# tempContr.net
KiCad netlist of a schematic drawn in Altium Designer
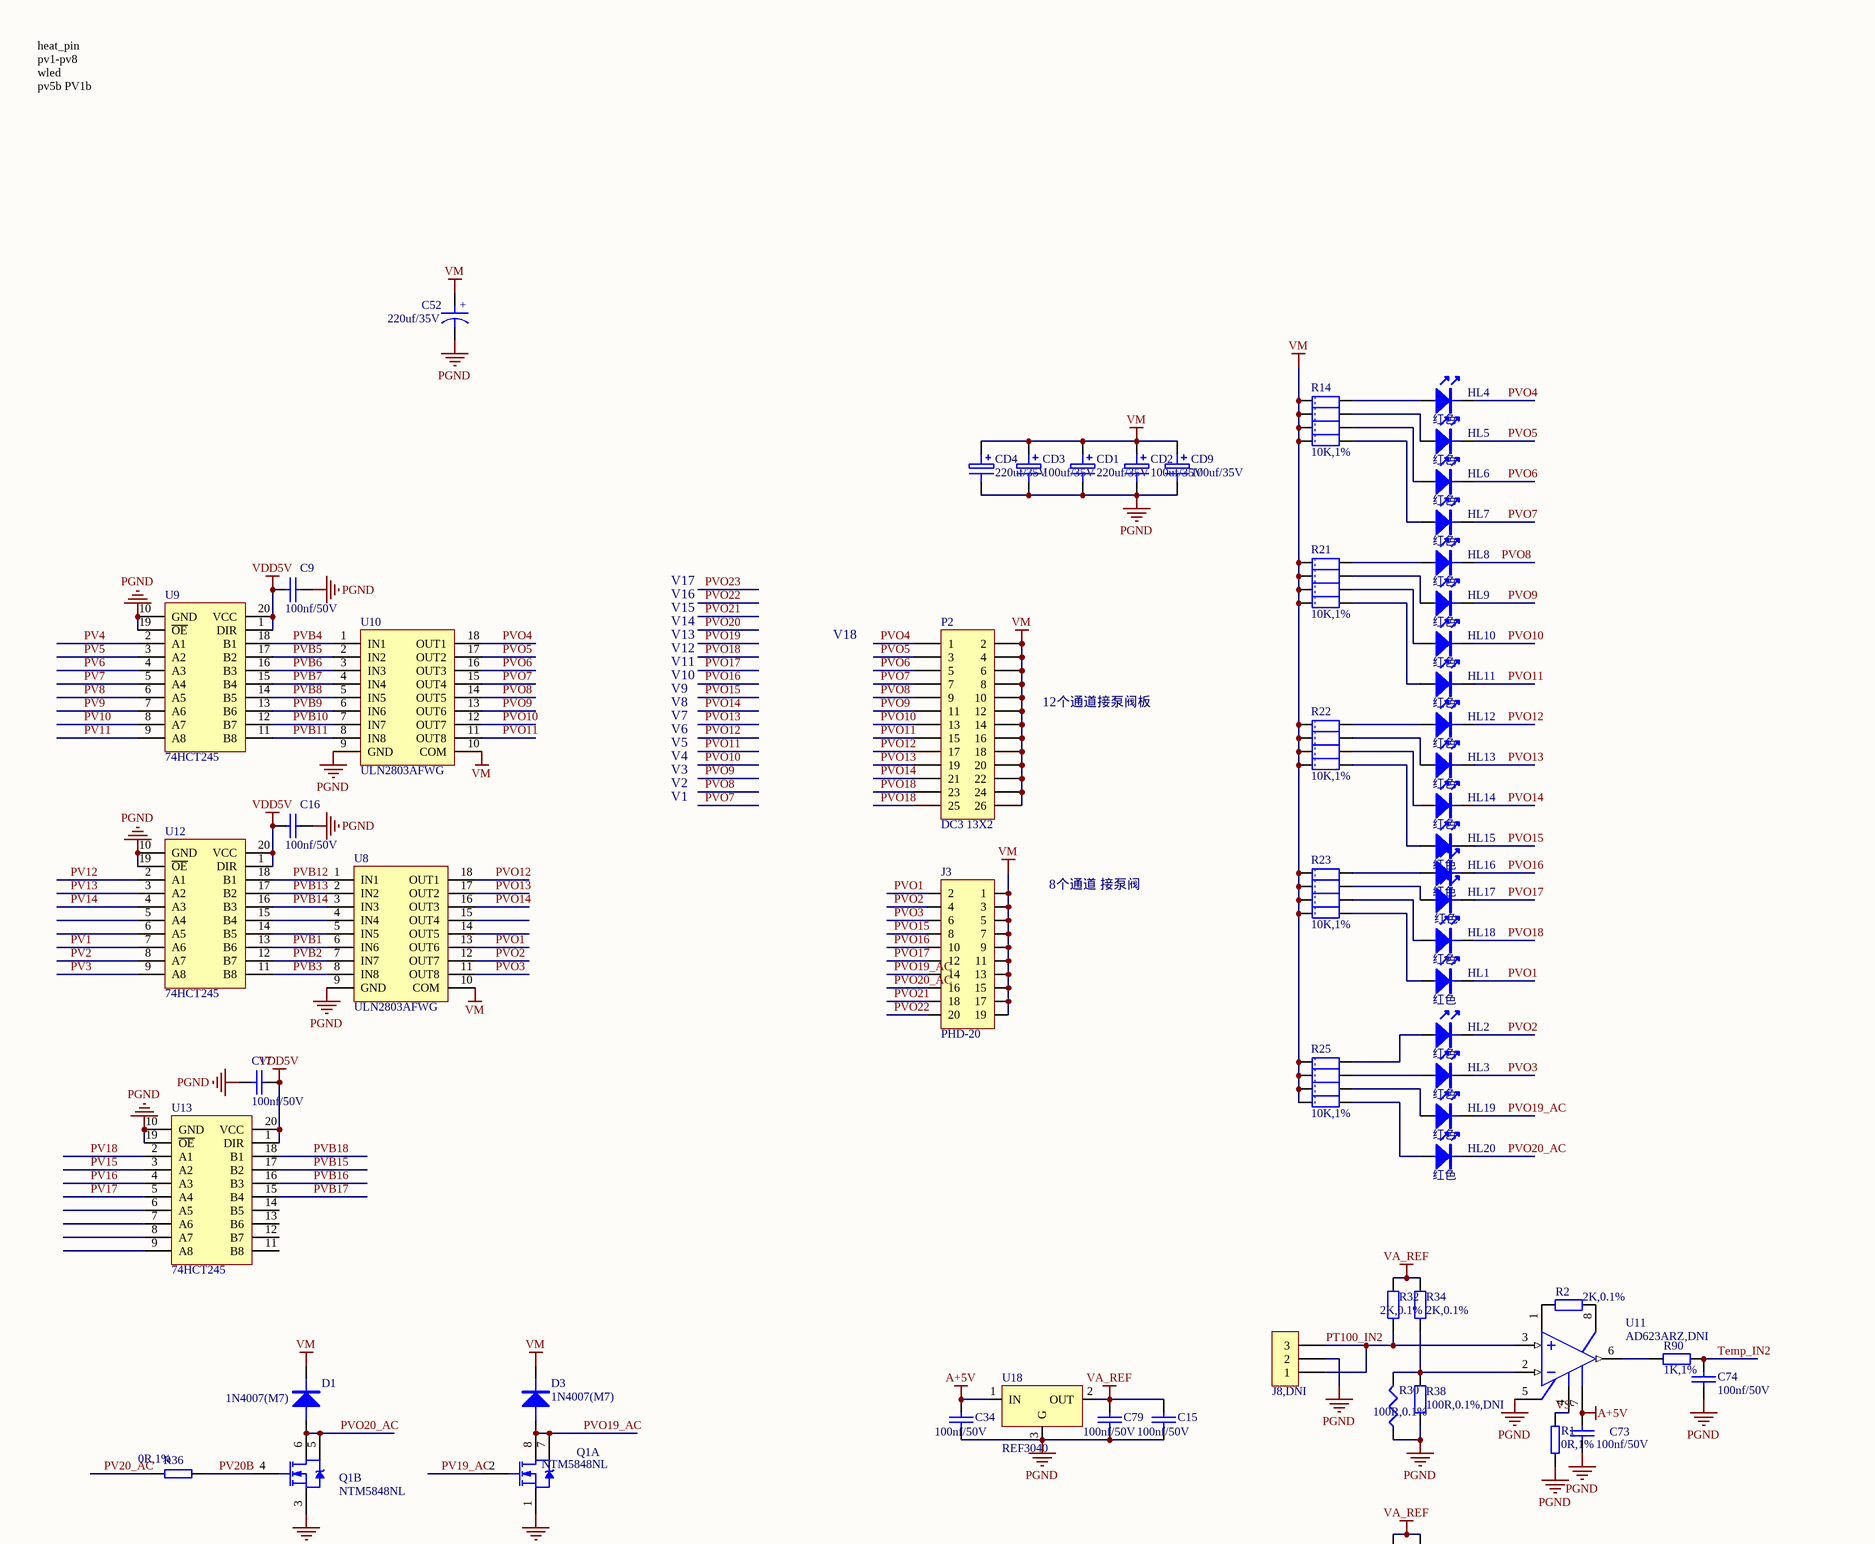
[diagram p0: tempContr.SchDoc, top left]
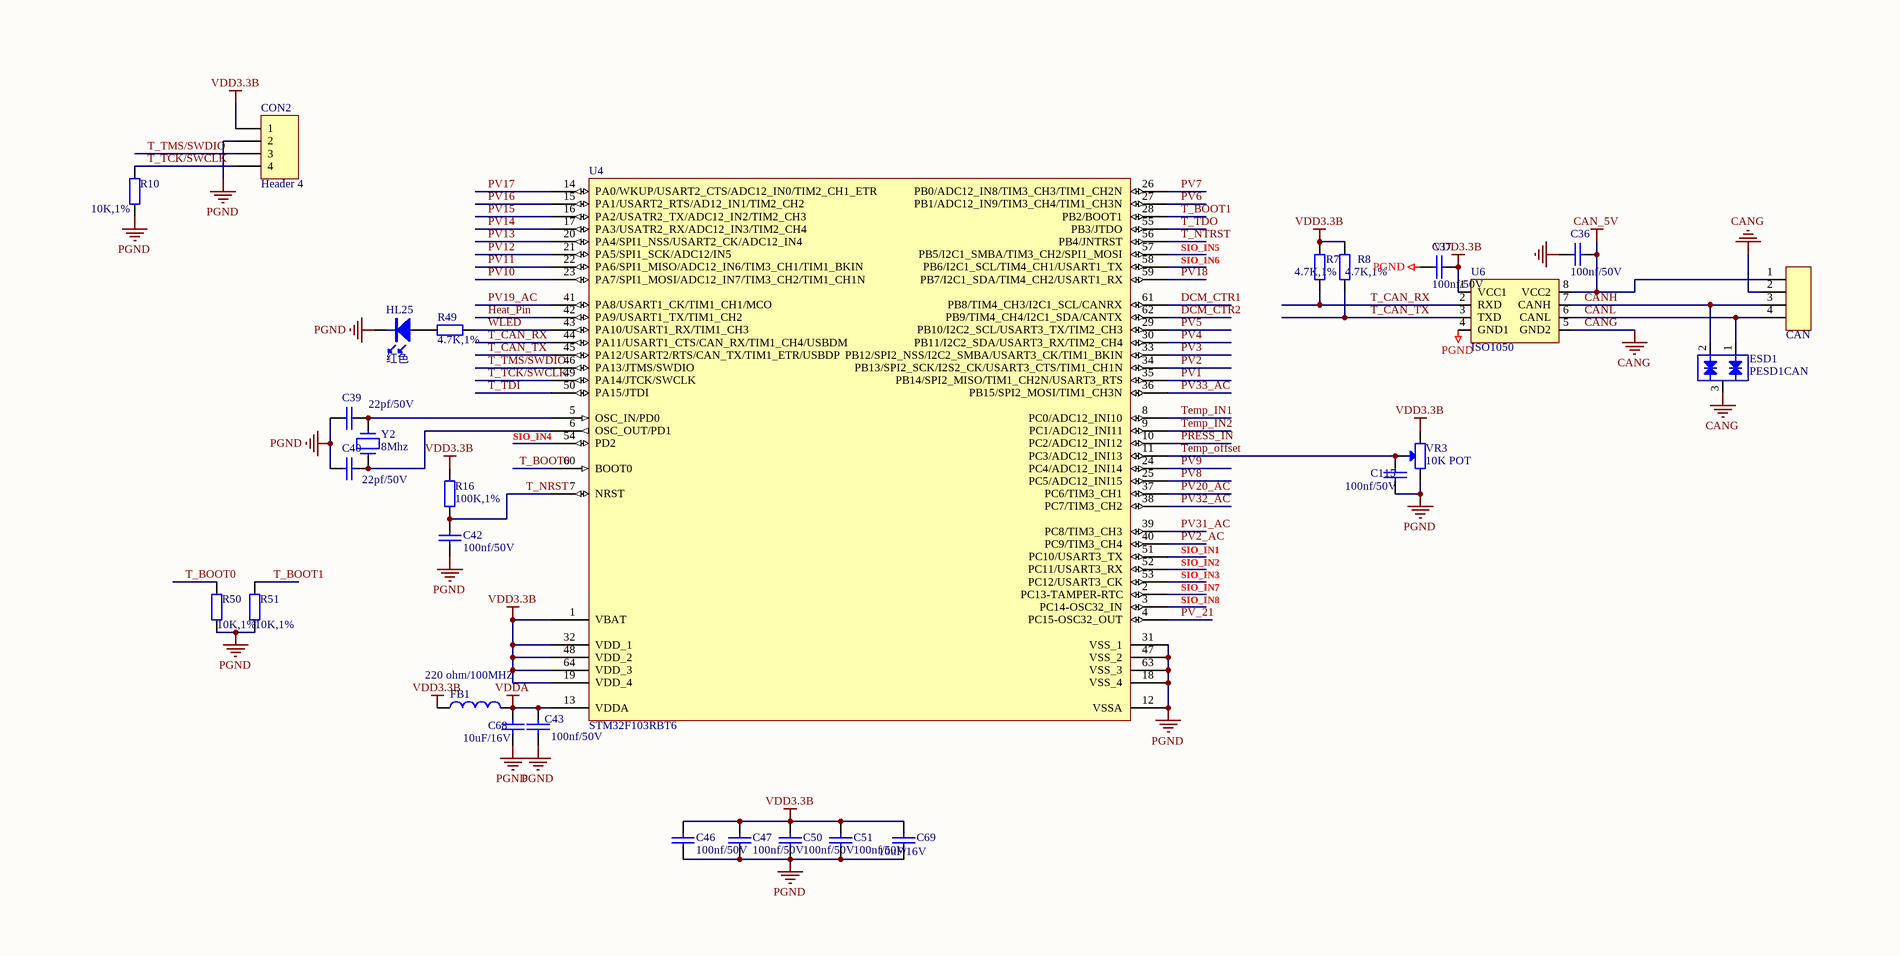
[diagram p1: tempContr.SchDoc, top right]
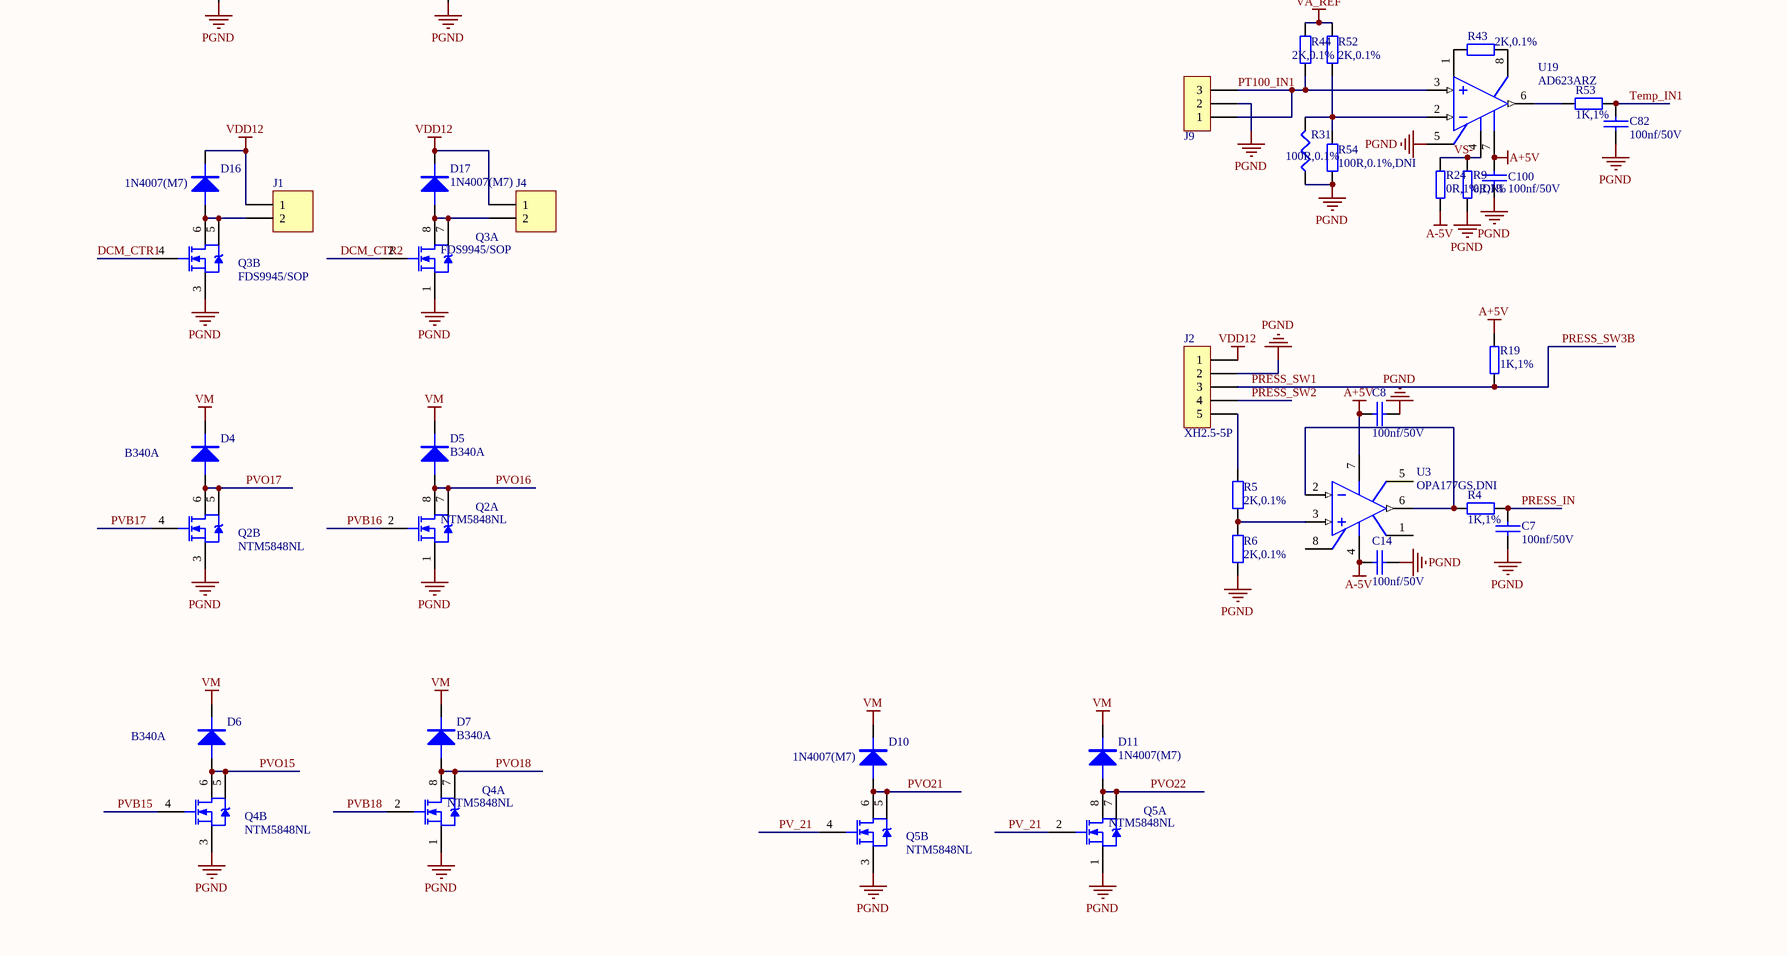
[diagram p2: tempContr.SchDoc, bottom left]
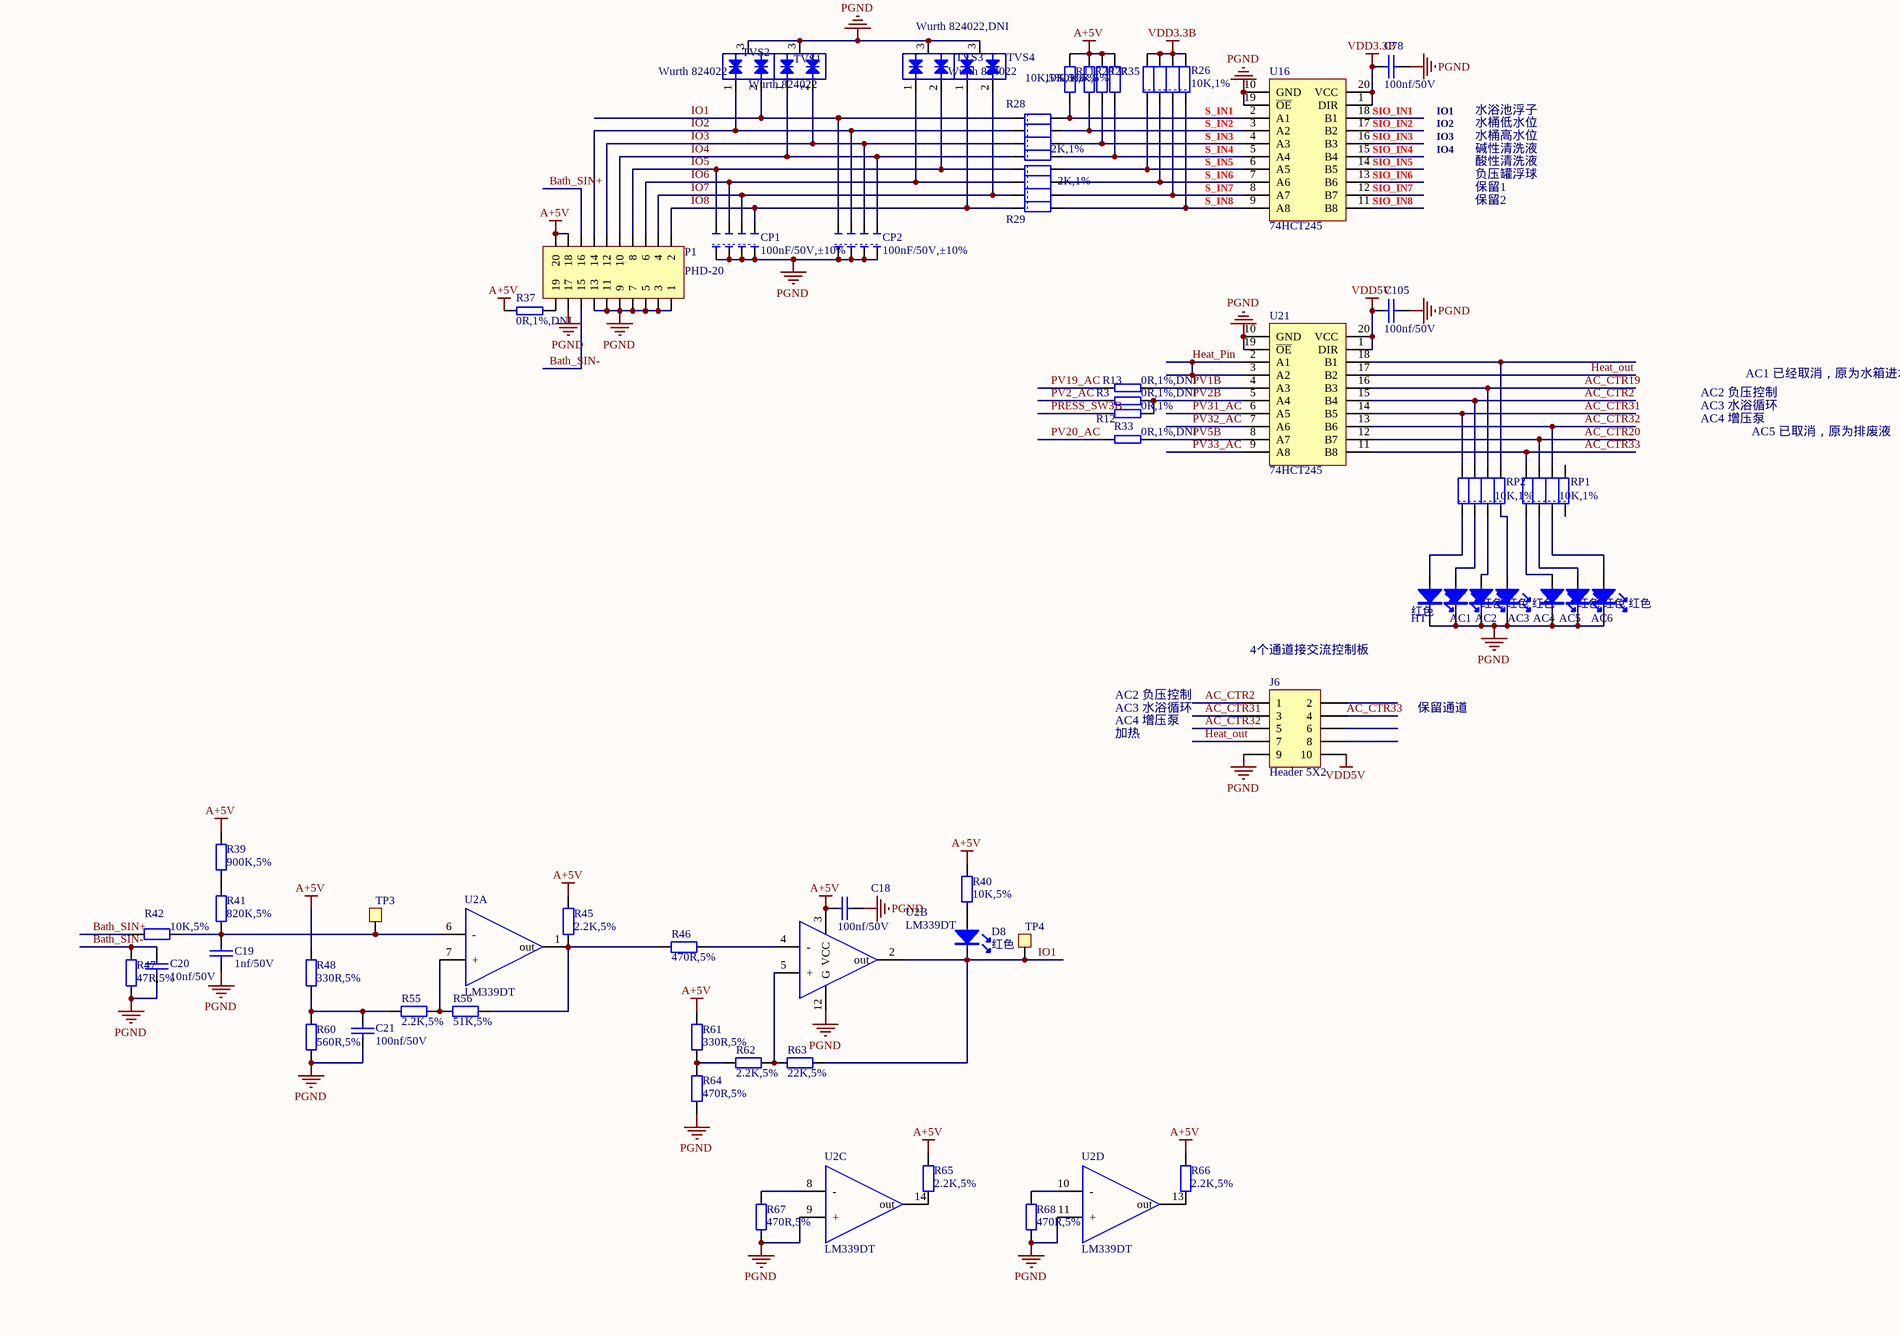
[diagram p3: tempContr.SchDoc, bottom right]

(export (version "E")
  (design (tool "Eeschema 10.0.6"))
  (components
    (comp (ref "AC1")
      (value "红色")
      (footprint "LED_0805")
      (description "Led")
      (fields (field (name "Comment") "LED,Red"))
      (libsource (lib "DiscreteCom") (part "LED"))
    )
    (comp (ref "AC2")
      (value "红色")
      (footprint "LED_0805")
      (description "Led")
      (fields (field (name "Comment") "LED,Red"))
      (libsource (lib "DiscreteCom") (part "LED"))
    )
    (comp (ref "AC3")
      (value "红色")
      (footprint "LED_0805")
      (description "Led")
      (fields (field (name "Comment") "LED,Red"))
      (libsource (lib "DiscreteCom") (part "LED"))
    )
    (comp (ref "AC4")
      (value "红色")
      (footprint "LED_0805")
      (description "Led")
      (fields (field (name "Comment") "LED,Red"))
      (libsource (lib "DiscreteCom") (part "LED"))
    )
    (comp (ref "AC5")
      (value "红色")
      (footprint "LED_0805")
      (description "Led")
      (fields (field (name "Comment") "LED,Red"))
      (libsource (lib "DiscreteCom") (part "LED"))
    )
    (comp (ref "AC6")
      (value "红色")
      (footprint "LED_0805")
      (description "Led")
      (fields (field (name "Comment") "LED,Red"))
      (libsource (lib "DiscreteCom") (part "LED"))
    )
    (comp (ref "C7")
      (value "100nf/50V")
      (footprint "0805")
      (description "Capacitor")
      (libsource (lib "DiscreteCom") (part "CAP"))
    )
    (comp (ref "C8")
      (value "100nf/50V")
      (footprint "0805")
      (description "Capacitor")
      (libsource (lib "*") (part "CAP"))
    )
    (comp (ref "C9")
      (value "100nf/50V")
      (footprint "0805")
      (description "Capacitor")
      (libsource (lib "*") (part "CAP"))
    )
    (comp (ref "C14")
      (value "100nf/50V")
      (footprint "0805")
      (description "Capacitor")
      (libsource (lib "*") (part "CAP"))
    )
    (comp (ref "C15")
      (value "100nf/50V")
      (footprint "0805")
      (description "Capacitor")
      (libsource (lib "*") (part "CAP"))
    )
    (comp (ref "C16")
      (value "100nf/50V")
      (footprint "0805")
      (description "Capacitor")
      (libsource (lib "*") (part "CAP"))
    )
    (comp (ref "C17")
      (value "100nf/50V")
      (footprint "0805")
      (description "Capacitor")
      (libsource (lib "*") (part "CAP"))
    )
    (comp (ref "C18")
      (value "100nf/50V")
      (footprint "0805")
      (description "Capacitor")
      (libsource (lib "DiscreteCom") (part "CAP"))
    )
    (comp (ref "C19")
      (value "1nf/50V")
      (footprint "0805")
      (description "Capacitor")
      (libsource (lib "DiscreteCom") (part "CAP"))
    )
    (comp (ref "C20")
      (value "10nf/50V")
      (footprint "0805")
      (description "Capacitor")
      (libsource (lib "DiscreteCom") (part "CAP"))
    )
    (comp (ref "C21")
      (value "100nf/50V")
      (footprint "0805")
      (description "Capacitor")
      (libsource (lib "DiscreteCom") (part "CAP"))
    )
    (comp (ref "C34")
      (value "100nf/50V")
      (footprint "0805")
      (description "Capacitor")
      (libsource (lib "*") (part "CAP"))
    )
    (comp (ref "C36")
      (value "100nf/50V")
      (footprint "0805")
      (description "Capacitor")
      (libsource (lib "DiscreteCom") (part "CAP"))
    )
    (comp (ref "C37")
      (value "100nf/50V")
      (footprint "0805")
      (description "Capacitor")
      (libsource (lib "DiscreteCom") (part "CAP"))
    )
    (comp (ref "C39")
      (value "22pf/50V")
      (footprint "0805")
      (description "Capacitor")
      (libsource (lib "DiscreteCom") (part "CAP"))
    )
    (comp (ref "C40")
      (value "22pf/50V")
      (footprint "0805")
      (description "Capacitor")
      (libsource (lib "DiscreteCom") (part "CAP"))
    )
    (comp (ref "C42")
      (value "100nf/50V")
      (footprint "0805")
      (description "Capacitor")
      (libsource (lib "DiscreteCom") (part "CAP"))
    )
    (comp (ref "C43")
      (value "100nf/50V")
      (footprint "0805")
      (description "Capacitor")
      (libsource (lib "DiscreteCom") (part "CAP"))
    )
    (comp (ref "C46")
      (value "100nf/50V")
      (footprint "0805")
      (description "Capacitor")
      (libsource (lib "DiscreteCom") (part "CAP"))
    )
    (comp (ref "C47")
      (value "100nf/50V")
      (footprint "0805")
      (description "Capacitor")
      (libsource (lib "DiscreteCom") (part "CAP"))
    )
    (comp (ref "C50")
      (value "100nf/50V")
      (footprint "0805")
      (description "Capacitor")
      (libsource (lib "DiscreteCom") (part "CAP"))
    )
    (comp (ref "C51")
      (value "100nf/50V")
      (footprint "0805")
      (description "Capacitor")
      (libsource (lib "DiscreteCom") (part "CAP"))
    )
    (comp (ref "C52")
      (value "220uf/35V")
      (footprint "CX8*10.5")
      (description "Capacitor")
      (libsource (lib "General") (part "CAPACITOR POL"))
    )
    (comp (ref "C68")
      (value "10uF/16V")
      (footprint "GeneralPcblib V0.1:1206")
      (description "Capacitor")
      (libsource (lib "General") (part "CAP"))
    )
    (comp (ref "C69")
      (value "10uF/16V")
      (footprint "GeneralPcblib V0.1:1206")
      (description "Capacitor")
      (libsource (lib "General") (part "CAP"))
    )
    (comp (ref "C73")
      (value "100nf/50V")
      (footprint "0805")
      (description "Capacitor")
      (libsource (lib "*") (part "CAP"))
    )
    (comp (ref "C74")
      (value "100nf/50V")
      (footprint "0805")
      (description "Capacitor")
      (libsource (lib "DiscreteCom") (part "CAP"))
    )
    (comp (ref "C78")
      (value "100nf/50V")
      (footprint "0805")
      (description "Capacitor")
      (libsource (lib "*") (part "CAP"))
    )
    (comp (ref "C79")
      (value "100nf/50V")
      (footprint "0805")
      (description "Capacitor")
      (libsource (lib "*") (part "CAP"))
    )
    (comp (ref "C82")
      (value "100nf/50V")
      (footprint "0805")
      (description "Capacitor")
      (libsource (lib "DiscreteCom") (part "CAP"))
    )
    (comp (ref "C100")
      (value "100nf/50V")
      (footprint "0805")
      (description "Capacitor")
      (libsource (lib "*") (part "CAP"))
    )
    (comp (ref "C105")
      (value "100nf/50V")
      (footprint "0805")
      (description "Capacitor")
      (libsource (lib "*") (part "CAP"))
    )
    (comp (ref "C115")
      (value "100nf/50V")
      (footprint "0805")
      (description "Capacitor")
      (libsource (lib "DiscreteCom") (part "CAP"))
    )
    (comp (ref "CAN")
      (value "XH2.54-4P")
      (footprint "GeneralPcblib V0.1:XH2.5-4P")
      (description "XH2.54-4P 针座")
      (libsource (lib "CON1") (part "XH2.54-4P"))
    )
    (comp (ref "CD1")
      (value "220uf/35V")
      (footprint "CX8*10.5")
      (description "Electrolytic Capacitor")
      (libsource (lib "DiscreteCom") (part "Capacitor Electrolytic"))
    )
    (comp (ref "CD2")
      (value "100uf/35V")
      (footprint "CX6.3*5.4")
      (description "Electrolytic Capacitor")
      (libsource (lib "DiscreteCom") (part "Capacitor Electrolytic"))
    )
    (comp (ref "CD3")
      (value "100uf/35V")
      (footprint "CX6.3*5.4")
      (description "Electrolytic Capacitor")
      (libsource (lib "DiscreteCom") (part "Capacitor Electrolytic"))
    )
    (comp (ref "CD4")
      (value "220uf/35V")
      (footprint "CX8*10.5")
      (description "Electrolytic Capacitor")
      (libsource (lib "DiscreteCom") (part "Capacitor Electrolytic"))
    )
    (comp (ref "CD9")
      (value "100uf/35V")
      (footprint "CX6.3*5.4")
      (description "Electrolytic Capacitor")
      (libsource (lib "DiscreteCom") (part "Capacitor Electrolytic"))
    )
    (comp (ref "CON2")
      (value "Header 4")
      (footprint "HDR1X4")
      (description "Header, 4-Pin")
      (fields (field (name "PUBLISHER") "Altium Limited"))
      (libsource (lib "Miscellaneous Connectors") (part "Header 4"))
    )
    (comp (ref "CP1")
      (value "100nF/50V,±10%")
      (footprint "8P4R_0603")
      (libsource (lib "DiscreteCom") (part "CAP 1*4"))
    )
    (comp (ref "CP2")
      (value "100nF/50V,±10%")
      (footprint "8P4R_0603")
      (libsource (lib "DiscreteCom") (part "CAP 1*4"))
    )
    (comp (ref "D1")
      (value "1N4007(M7)")
      (footprint "GeneralPcblib V0.1:SMA(AK)")
      (description "Diode")
      (libsource (lib "General") (part "DIODE"))
    )
    (comp (ref "D3")
      (value "1N4007(M7)")
      (footprint "GeneralPcblib V0.1:SMA(AK)")
      (description "Diode")
      (libsource (lib "General") (part "DIODE"))
    )
    (comp (ref "D4")
      (value "B340A")
      (footprint "GeneralPcblib V0.1:SMA(AK)")
      (description "Diode")
      (libsource (lib "General") (part "DIODE"))
    )
    (comp (ref "D5")
      (value "B340A")
      (footprint "GeneralPcblib V0.1:SMA(AK)")
      (description "Diode")
      (libsource (lib "General") (part "DIODE"))
    )
    (comp (ref "D6")
      (value "B340A")
      (footprint "GeneralPcblib V0.1:SMA(AK)")
      (description "Diode")
      (libsource (lib "General") (part "DIODE"))
    )
    (comp (ref "D7")
      (value "B340A")
      (footprint "GeneralPcblib V0.1:SMA(AK)")
      (description "Diode")
      (libsource (lib "General") (part "DIODE"))
    )
    (comp (ref "D8")
      (value "红色")
      (footprint "LED_0805")
      (description "Led")
      (fields (field (name "Comment") "LED"))
      (libsource (lib "") (part "LED_1"))
    )
    (comp (ref "D10")
      (value "1N4007(M7)")
      (footprint "GeneralPcblib V0.1:SMA(AK)")
      (description "Diode")
      (libsource (lib "General") (part "DIODE"))
    )
    (comp (ref "D11")
      (value "1N4007(M7)")
      (footprint "GeneralPcblib V0.1:SMA(AK)")
      (description "Diode")
      (libsource (lib "General") (part "DIODE"))
    )
    (comp (ref "D16")
      (value "1N4007(M7)")
      (footprint "GeneralPcblib V0.1:SMA(AK)")
      (description "Diode")
      (libsource (lib "General") (part "DIODE"))
    )
    (comp (ref "D17")
      (value "1N4007(M7)")
      (footprint "GeneralPcblib V0.1:SMA(AK)")
      (description "Diode")
      (libsource (lib "General") (part "DIODE"))
    )
    (comp (ref "ESD1")
      (value "PESD1CAN")
      (footprint "SOT233")
      (description "Diode")
      (libsource (lib "DiscreteCom") (part "TVS-2"))
    )
    (comp (ref "FB1")
      (value "220 ohm/100MHZ")
      (footprint "GeneralPcblib V0.1:0805")
      (description "Inductor")
      (libsource (lib "DiscreteCom") (part "INDUCTOR"))
    )
    (comp (ref "HL1")
      (value "红色")
      (footprint "LED_0805")
      (description "Led")
      (fields (field (name "Comment") "LED,Red"))
      (libsource (lib "DiscreteCom") (part "LED"))
    )
    (comp (ref "HL2")
      (value "红色")
      (footprint "LED_0805")
      (description "Led")
      (fields (field (name "Comment") "LED,Red"))
      (libsource (lib "DiscreteCom") (part "LED"))
    )
    (comp (ref "HL3")
      (value "红色")
      (footprint "LED_0805")
      (description "Led")
      (fields (field (name "Comment") "LED,Red"))
      (libsource (lib "DiscreteCom") (part "LED"))
    )
    (comp (ref "HL4")
      (value "红色")
      (footprint "LED_0805")
      (description "Led")
      (fields (field (name "Comment") "LED,Red"))
      (libsource (lib "DiscreteCom") (part "LED"))
    )
    (comp (ref "HL5")
      (value "红色")
      (footprint "LED_0805")
      (description "Led")
      (fields (field (name "Comment") "LED,Red"))
      (libsource (lib "DiscreteCom") (part "LED"))
    )
    (comp (ref "HL6")
      (value "红色")
      (footprint "LED_0805")
      (description "Led")
      (fields (field (name "Comment") "LED,Red"))
      (libsource (lib "DiscreteCom") (part "LED"))
    )
    (comp (ref "HL7")
      (value "红色")
      (footprint "LED_0805")
      (description "Led")
      (fields (field (name "Comment") "LED,Red"))
      (libsource (lib "DiscreteCom") (part "LED"))
    )
    (comp (ref "HL8")
      (value "红色")
      (footprint "LED_0805")
      (description "Led")
      (fields (field (name "Comment") "LED,Red"))
      (libsource (lib "DiscreteCom") (part "LED"))
    )
    (comp (ref "HL9")
      (value "红色")
      (footprint "LED_0805")
      (description "Led")
      (fields (field (name "Comment") "LED,Red"))
      (libsource (lib "DiscreteCom") (part "LED"))
    )
    (comp (ref "HL10")
      (value "红色")
      (footprint "LED_0805")
      (description "Led")
      (fields (field (name "Comment") "LED,Red"))
      (libsource (lib "DiscreteCom") (part "LED"))
    )
    (comp (ref "HL11")
      (value "红色")
      (footprint "LED_0805")
      (description "Led")
      (fields (field (name "Comment") "LED,Red"))
      (libsource (lib "DiscreteCom") (part "LED"))
    )
    (comp (ref "HL12")
      (value "红色")
      (footprint "LED_0805")
      (description "Led")
      (fields (field (name "Comment") "LED,Red"))
      (libsource (lib "DiscreteCom") (part "LED"))
    )
    (comp (ref "HL13")
      (value "红色")
      (footprint "LED_0805")
      (description "Led")
      (fields (field (name "Comment") "LED,Red"))
      (libsource (lib "DiscreteCom") (part "LED"))
    )
    (comp (ref "HL14")
      (value "红色")
      (footprint "LED_0805")
      (description "Led")
      (fields (field (name "Comment") "LED,Red"))
      (libsource (lib "DiscreteCom") (part "LED"))
    )
    (comp (ref "HL15")
      (value "红色")
      (footprint "LED_0805")
      (description "Led")
      (fields (field (name "Comment") "LED,Red"))
      (libsource (lib "DiscreteCom") (part "LED"))
    )
    (comp (ref "HL16")
      (value "红色")
      (footprint "LED_0805")
      (description "Led")
      (fields (field (name "Comment") "LED,Red"))
      (libsource (lib "DiscreteCom") (part "LED"))
    )
    (comp (ref "HL17")
      (value "红色")
      (footprint "LED_0805")
      (description "Led")
      (fields (field (name "Comment") "LED,Red"))
      (libsource (lib "DiscreteCom") (part "LED"))
    )
    (comp (ref "HL18")
      (value "红色")
      (footprint "LED_0805")
      (description "Led")
      (fields (field (name "Comment") "LED,Red"))
      (libsource (lib "DiscreteCom") (part "LED"))
    )
    (comp (ref "HL19")
      (value "红色")
      (footprint "LED_0805")
      (description "Led")
      (fields (field (name "Comment") "LED,Red"))
      (libsource (lib "DiscreteCom") (part "LED"))
    )
    (comp (ref "HL20")
      (value "红色")
      (footprint "LED_0805")
      (description "Led")
      (fields (field (name "Comment") "LED,Red"))
      (libsource (lib "DiscreteCom") (part "LED"))
    )
    (comp (ref "HL25")
      (value "红色")
      (footprint "LED_0805")
      (description "Led")
      (fields (field (name "Comment") "LED,Red"))
      (libsource (lib "DiscreteCom") (part "LED"))
    )
    (comp (ref "HT")
      (value "红色")
      (footprint "LED_0805")
      (description "Led")
      (fields (field (name "Comment") "LED,Red"))
      (libsource (lib "DiscreteCom") (part "LED"))
    )
    (comp (ref "J1")
      (value "XH2.54-2P")
      (footprint "GeneralPcblib V0.1:XH2.5-2P")
      (description "XH2.54-2P 针座")
      (fields (field (name "PUBLISHER") "Altium Limited"))
      (libsource (lib "CON1") (part "XH2.54-2P"))
    )
    (comp (ref "J2")
      (value "XH2.5-5P")
      (footprint "GeneralPcblib V0.1:XH2.5-5P")
      (description "XH2.5-5P 针座")
      (libsource (lib "CON1") (part "XH2.54-5P"))
    )
    (comp (ref "J3")
      (value "PHD-20")
      (footprint "PHD-20")
      (description "PHD-20针座")
      (fields (field (name "PUBLISHER") "Altium Limited"))
      (libsource (lib "CON1") (part "PHD-20"))
    )
    (comp (ref "J4")
      (value "XH2.54-2P")
      (footprint "GeneralPcblib V0.1:XH2.5-2P")
      (description "XH2.54-2P 针座")
      (fields (field (name "PUBLISHER") "Altium Limited"))
      (libsource (lib "CON1") (part "XH2.54-2P"))
    )
    (comp (ref "J6")
      (value "Header 5X2")
      (footprint "DC3-10")
      (description "Header, 5-Pin, Dual row")
      (fields (field (name "PUBLISHER") "Altium Limited"))
      (libsource (lib "Miscellaneous Connectors") (part "Header 5X2"))
    )
    (comp (ref "J8,DNI")
      (value "XH2.54-3P")
      (footprint "GeneralPcblib V0.1:XH2.5-3P")
      (description "XH2.54-3P 针座")
      (libsource (lib "CON1") (part "XH2.54-3P"))
    )
    (comp (ref "J9")
      (value "XH2.54-3P")
      (footprint "GeneralPcblib V0.1:XH2.5-3P")
      (description "XH2.54-3P 针座")
      (libsource (lib "CON1") (part "XH2.54-3P"))
    )
    (comp (ref "P1")
      (value "PHD-20")
      (footprint "PHD-20")
      (description "PHD-20针座")
      (fields (field (name "PUBLISHER") "Altium Limited"))
      (libsource (lib "") (part "PHD-20_1"))
    )
    (comp (ref "P2")
      (value "DC3 13X2")
      (footprint "GeneralPcblib V0.1:DC3-2X13")
      (description "Header, 13-Pin, Dual row")
      (fields (field (name "PUBLISHER") "Altium Limited"))
      (libsource (lib "Miscellaneous Connectors") (part "Header 13X2"))
    )
    (comp (ref "Q1")
      (value "NTM5848NL")
      (footprint "SOIC8")
      (description "N-Channel Power MOSFET")
      (fields (field (name "PUBLISHER") "Altium Limited"))
      (libsource (lib "DiscreteCom") (part "NMOS-9945"))
    )
    (comp (ref "Q2")
      (value "NTM5848NL")
      (footprint "SOIC8")
      (description "N-Channel Power MOSFET")
      (fields (field (name "PUBLISHER") "Altium Limited"))
      (libsource (lib "DiscreteCom") (part "NMOS-9945"))
    )
    (comp (ref "Q3")
      (value "FDS9945/SOP")
      (footprint "SOIC8")
      (description "N-Channel Power MOSFET")
      (fields (field (name "PUBLISHER") "Altium Limited"))
      (libsource (lib "DiscreteCom") (part "NMOS-9945"))
    )
    (comp (ref "Q4")
      (value "NTM5848NL")
      (footprint "SOIC8")
      (description "N-Channel Power MOSFET")
      (fields (field (name "PUBLISHER") "Altium Limited"))
      (libsource (lib "DiscreteCom") (part "NMOS-9945"))
    )
    (comp (ref "Q5")
      (value "NTM5848NL")
      (footprint "SOIC8")
      (description "N-Channel Power MOSFET")
      (fields (field (name "PUBLISHER") "Altium Limited"))
      (libsource (lib "DiscreteCom") (part "NMOS-9945"))
    )
    (comp (ref "R1")
      (value "0R,1%")
      (footprint "GeneralPcblib V0.1:0805")
      (description "R")
      (libsource (lib "DiscreteCom") (part "Resistor"))
    )
    (comp (ref "R2")
      (value "2K,0.1%")
      (footprint "0805")
      (description "Semiconductor Resistor")
      (fields (field (name "PUBLISHER") "Altium Limited"))
      (libsource (lib "") (part "Res Semi_1"))
    )
    (comp (ref "R3")
      (value "0R,1%,DNI")
      (footprint "GeneralPcblib V0.1:0805")
      (description "R")
      (libsource (lib "DiscreteCom") (part "Resistor"))
    )
    (comp (ref "R4")
      (value "1K,1%")
      (footprint "0805")
      (description "Resistor")
      (fields (field (name "PUBLISHER") "Altium Limited"))
      (libsource (lib "General") (part "Res2"))
    )
    (comp (ref "R5")
      (value "2K,0.1%")
      (footprint "0805")
      (description "Semiconductor Resistor")
      (fields (field (name "PUBLISHER") "Altium Limited"))
      (libsource (lib "Miscellaneous Devices") (part "Res Semi"))
    )
    (comp (ref "R6")
      (value "2K,0.1%")
      (footprint "0805")
      (description "Semiconductor Resistor")
      (fields (field (name "PUBLISHER") "Altium Limited"))
      (libsource (lib "Miscellaneous Devices") (part "Res Semi"))
    )
    (comp (ref "R7")
      (value "4.7K,1%")
      (footprint "0805")
      (description "Resistor")
      (fields (field (name "PUBLISHER") "Altium Limited"))
      (libsource (lib "") (part "Res2_1"))
    )
    (comp (ref "R8")
      (value "4.7K,1%")
      (footprint "0805")
      (description "Resistor")
      (fields (field (name "PUBLISHER") "Altium Limited"))
      (libsource (lib "") (part "Res2_1"))
    )
    (comp (ref "R9")
      (value "0R,1%")
      (footprint "GeneralPcblib V0.1:0805")
      (description "R")
      (libsource (lib "DiscreteCom") (part "Resistor"))
    )
    (comp (ref "R10")
      (value "10K,1%")
      (footprint "0805")
      (description "Resistor")
      (fields (field (name "PUBLISHER") "Altium Limited"))
      (libsource (lib "*") (part "Res2"))
    )
    (comp (ref "R11")
      (value "10K,5%")
      (footprint "0805")
      (description "Resistor")
      (fields (field (name "PUBLISHER") "Altium Limited"))
      (libsource (lib "DiscreteCom") (part "Res2"))
    )
    (comp (ref "R12")
      (value "0R,1%")
      (footprint "GeneralPcblib V0.1:0805")
      (description "R")
      (libsource (lib "DiscreteCom") (part "Resistor"))
    )
    (comp (ref "R13")
      (value "0R,1%,DNI")
      (footprint "GeneralPcblib V0.1:0805")
      (description "R")
      (libsource (lib "DiscreteCom") (part "Resistor"))
    )
    (comp (ref "R14")
      (value "10K,1%")
      (footprint "8P4R_0603")
      (libsource (lib "DiscreteCom") (part "RES 1*4"))
    )
    (comp (ref "R16")
      (value "100K,1%")
      (footprint "0805")
      (description "Resistor")
      (fields (field (name "PUBLISHER") "Altium Limited"))
      (libsource (lib "") (part "Res2_1"))
    )
    (comp (ref "R19")
      (value "1K,1%")
      (footprint "GeneralPcblib V0.1:0805")
      (description "R")
      (libsource (lib "DiscreteCom") (part "Resistor"))
    )
    (comp (ref "R20")
      (value "10K,5%")
      (footprint "0805")
      (description "Resistor")
      (fields (field (name "PUBLISHER") "Altium Limited"))
      (libsource (lib "DiscreteCom") (part "Res2"))
    )
    (comp (ref "R21")
      (value "10K,1%")
      (footprint "8P4R_0603")
      (libsource (lib "DiscreteCom") (part "RES 1*4"))
    )
    (comp (ref "R22")
      (value "10K,1%")
      (footprint "8P4R_0603")
      (libsource (lib "DiscreteCom") (part "RES 1*4"))
    )
    (comp (ref "R23")
      (value "10K,1%")
      (footprint "8P4R_0603")
      (libsource (lib "DiscreteCom") (part "RES 1*4"))
    )
    (comp (ref "R24")
      (value "0R,1%,DNI")
      (footprint "GeneralPcblib V0.1:0805")
      (description "R")
      (libsource (lib "DiscreteCom") (part "Resistor"))
    )
    (comp (ref "R25")
      (value "10K,1%")
      (footprint "8P4R_0603")
      (libsource (lib "DiscreteCom") (part "RES 1*4"))
    )
    (comp (ref "R26")
      (value "10K,1%")
      (footprint "8P4R_0603")
      (libsource (lib "DiscreteCom") (part "RES 1*4"))
    )
    (comp (ref "R27")
      (value "10K,5%")
      (footprint "0805")
      (description "Resistor")
      (fields (field (name "PUBLISHER") "Altium Limited"))
      (libsource (lib "DiscreteCom") (part "Res2"))
    )
    (comp (ref "R28")
      (value "2K,1%")
      (footprint "8P4R_0603")
      (libsource (lib "DiscreteCom") (part "RES 1*4"))
    )
    (comp (ref "R29")
      (value "2K,1%")
      (footprint "8P4R_0603")
      (libsource (lib "DiscreteCom") (part "RES 1*4"))
    )
    (comp (ref "R30")
      (value "100R,0.1%")
      (footprint "GeneralPcblib V0.1:AXIAL-0.4")
      (description "Resistor")
      (libsource (lib "DiscreteCom") (part "RES1"))
    )
    (comp (ref "R31")
      (value "100R,0.1%")
      (footprint "GeneralPcblib V0.1:AXIAL-0.4")
      (description "Resistor")
      (libsource (lib "DiscreteCom") (part "RES1"))
    )
    (comp (ref "R32")
      (value "2K,0.1%")
      (footprint "0805")
      (description "Semiconductor Resistor")
      (fields (field (name "PUBLISHER") "Altium Limited"))
      (libsource (lib "Miscellaneous Devices") (part "Res Semi"))
    )
    (comp (ref "R33")
      (value "0R,1%,DNI")
      (footprint "GeneralPcblib V0.1:0805")
      (description "R")
      (libsource (lib "DiscreteCom") (part "Resistor"))
    )
    (comp (ref "R34")
      (value "2K,0.1%")
      (footprint "0805")
      (description "Semiconductor Resistor")
      (fields (field (name "PUBLISHER") "Altium Limited"))
      (libsource (lib "Miscellaneous Devices") (part "Res Semi"))
    )
    (comp (ref "R35")
      (value "10K,5%")
      (footprint "0805")
      (description "Resistor")
      (fields (field (name "PUBLISHER") "Altium Limited"))
      (libsource (lib "DiscreteCom") (part "Res2"))
    )
    (comp (ref "R36")
      (value "0R,1%")
      (footprint "GeneralPcblib V0.1:0805")
      (description "R")
      (libsource (lib "DiscreteCom") (part "Resistor"))
    )
    (comp (ref "R37")
      (value "0R,1%,DNI")
      (footprint "GeneralPcblib V0.1:0805")
      (description "R")
      (libsource (lib "DiscreteCom") (part "Resistor"))
    )
    (comp (ref "R38")
      (value "100R,0.1%,DNI")
      (footprint "0805")
      (description "Semiconductor Resistor")
      (fields (field (name "PUBLISHER") "Altium Limited"))
      (libsource (lib "Miscellaneous Devices") (part "Res Semi"))
    )
    (comp (ref "R39")
      (value "900K,5%")
      (footprint "0805")
      (description "Resistor")
      (fields (field (name "PUBLISHER") "Altium Limited"))
      (libsource (lib "") (part "Res2_1"))
    )
    (comp (ref "R40")
      (value "10K,5%")
      (footprint "0805")
      (description "Resistor")
      (fields (field (name "PUBLISHER") "Altium Limited"))
      (libsource (lib "DiscreteCom") (part "Res2"))
    )
    (comp (ref "R41")
      (value "820K,5%")
      (footprint "0805")
      (description "Resistor")
      (fields (field (name "PUBLISHER") "Altium Limited"))
      (libsource (lib "") (part "Res2_1"))
    )
    (comp (ref "R42")
      (value "10K,5%")
      (footprint "0805")
      (description "Resistor")
      (fields (field (name "PUBLISHER") "Altium Limited"))
      (libsource (lib "") (part "Res2_3"))
    )
    (comp (ref "R43")
      (value "2K,0.1%")
      (footprint "0805")
      (description "Semiconductor Resistor")
      (fields (field (name "PUBLISHER") "Altium Limited"))
      (libsource (lib "") (part "Res Semi_1"))
    )
    (comp (ref "R44")
      (value "2K,0.1%")
      (footprint "0805")
      (description "Semiconductor Resistor")
      (fields (field (name "PUBLISHER") "Altium Limited"))
      (libsource (lib "Miscellaneous Devices") (part "Res Semi"))
    )
    (comp (ref "R45")
      (value "2.2K,5%")
      (footprint "0805")
      (description "Resistor")
      (fields (field (name "PUBLISHER") "Altium Limited"))
      (libsource (lib "DiscreteCom") (part "Res2"))
    )
    (comp (ref "R46")
      (value "470R,5%")
      (footprint "0805")
      (description "Resistor")
      (fields (field (name "PUBLISHER") "Altium Limited"))
      (libsource (lib "") (part "Res2_2"))
    )
    (comp (ref "R47")
      (value "47R,5%")
      (footprint "0805")
      (description "Resistor")
      (fields (field (name "PUBLISHER") "Altium Limited"))
      (libsource (lib "") (part "Res2_1"))
    )
    (comp (ref "R48")
      (value "330R,5%")
      (footprint "0805")
      (description "Resistor")
      (fields (field (name "PUBLISHER") "Altium Limited"))
      (libsource (lib "") (part "Res2_1"))
    )
    (comp (ref "R49")
      (value "4.7K,1%")
      (footprint "0805")
      (description "Resistor")
      (fields (field (name "PUBLISHER") "Altium Limited"))
      (libsource (lib "") (part "Res2_2"))
    )
    (comp (ref "R50")
      (value "10K,1%")
      (footprint "0805")
      (description "Resistor")
      (fields (field (name "PUBLISHER") "Altium Limited"))
      (libsource (lib "*") (part "Res2"))
    )
    (comp (ref "R51")
      (value "10K,1%")
      (footprint "0805")
      (description "Resistor")
      (fields (field (name "PUBLISHER") "Altium Limited"))
      (libsource (lib "*") (part "Res2"))
    )
    (comp (ref "R52")
      (value "2K,0.1%")
      (footprint "0805")
      (description "Semiconductor Resistor")
      (fields (field (name "PUBLISHER") "Altium Limited"))
      (libsource (lib "Miscellaneous Devices") (part "Res Semi"))
    )
    (comp (ref "R53")
      (value "1K,1%")
      (footprint "0805")
      (description "Resistor")
      (fields (field (name "PUBLISHER") "Altium Limited"))
      (libsource (lib "General") (part "Res2"))
    )
    (comp (ref "R54")
      (value "100R,0.1%,DNI")
      (footprint "0805")
      (description "Semiconductor Resistor")
      (fields (field (name "PUBLISHER") "Altium Limited"))
      (libsource (lib "Miscellaneous Devices") (part "Res Semi"))
    )
    (comp (ref "R55")
      (value "2.2K,5%")
      (footprint "0805")
      (description "Resistor")
      (fields (field (name "PUBLISHER") "Altium Limited"))
      (libsource (lib "") (part "Res2_2"))
    )
    (comp (ref "R56")
      (value "51K,5%")
      (footprint "0805")
      (description "Resistor")
      (fields (field (name "PUBLISHER") "Altium Limited"))
      (libsource (lib "") (part "Res2_2"))
    )
    (comp (ref "R60")
      (value "560R,5%")
      (footprint "0805")
      (description "Resistor")
      (fields (field (name "PUBLISHER") "Altium Limited"))
      (libsource (lib "") (part "Res2_1"))
    )
    (comp (ref "R61")
      (value "330R,5%")
      (footprint "0805")
      (description "Resistor")
      (fields (field (name "PUBLISHER") "Altium Limited"))
      (libsource (lib "") (part "Res2_1"))
    )
    (comp (ref "R62")
      (value "2.2K,5%")
      (footprint "0805")
      (description "Resistor")
      (fields (field (name "PUBLISHER") "Altium Limited"))
      (libsource (lib "") (part "Res2_2"))
    )
    (comp (ref "R63")
      (value "22K,5%")
      (footprint "0805")
      (description "Resistor")
      (fields (field (name "PUBLISHER") "Altium Limited"))
      (libsource (lib "") (part "Res2_2"))
    )
    (comp (ref "R64")
      (value "470R,5%")
      (footprint "0805")
      (description "Resistor")
      (fields (field (name "PUBLISHER") "Altium Limited"))
      (libsource (lib "") (part "Res2_1"))
    )
    (comp (ref "R65")
      (value "2.2K,5%")
      (footprint "0805")
      (description "Resistor")
      (fields (field (name "PUBLISHER") "Altium Limited"))
      (libsource (lib "DiscreteCom") (part "Res2"))
    )
    (comp (ref "R66")
      (value "2.2K,5%")
      (footprint "0805")
      (description "Resistor")
      (fields (field (name "PUBLISHER") "Altium Limited"))
      (libsource (lib "DiscreteCom") (part "Res2"))
    )
    (comp (ref "R67")
      (value "470R,5%")
      (footprint "0805")
      (description "Resistor")
      (fields (field (name "PUBLISHER") "Altium Limited"))
      (libsource (lib "") (part "Res2_1"))
    )
    (comp (ref "R68")
      (value "470R,5%")
      (footprint "0805")
      (description "Resistor")
      (fields (field (name "PUBLISHER") "Altium Limited"))
      (libsource (lib "") (part "Res2_1"))
    )
    (comp (ref "R90")
      (value "1K,1%")
      (footprint "0805")
      (description "Resistor")
      (fields (field (name "PUBLISHER") "Altium Limited"))
      (libsource (lib "General") (part "Res2"))
    )
    (comp (ref "RP1")
      (value "10K,1%")
      (footprint "8P4R_0603")
      (libsource (lib "DiscreteCom") (part "RES 1*4"))
    )
    (comp (ref "RP2")
      (value "10K,1%")
      (footprint "8P4R_0603")
      (libsource (lib "DiscreteCom") (part "RES 1*4"))
    )
    (comp (ref "TP3")
      (value "TP")
      (footprint "TP1")
      (description "Connector")
      (libsource (lib "DiscreteCom") (part "TP"))
    )
    (comp (ref "TP4")
      (value "TP")
      (footprint "TP1")
      (description "Connector")
      (libsource (lib "DiscreteCom") (part "TP"))
    )
    (comp (ref "TVS1")
      (value "Wurth 824022")
      (footprint "SOT233")
      (description "Diode")
      (libsource (lib "DiscreteCom") (part "TVS-2"))
    )
    (comp (ref "TVS2")
      (value "Wurth 824022")
      (footprint "SOT233")
      (description "Diode")
      (libsource (lib "DiscreteCom") (part "TVS-2"))
    )
    (comp (ref "TVS3")
      (value "Wurth 824022")
      (footprint "GeneralPcblib V0.1:SOT233")
      (description "Diode")
      (libsource (lib "DiscreteCom") (part "TVS-2"))
    )
    (comp (ref "TVS4")
      (value "Wurth 824022,DNI")
      (footprint "SOT233")
      (description "Diode")
      (libsource (lib "DiscreteCom") (part "TVS-2"))
    )
    (comp (ref "U2") (value "LM339DT") (footprint "SOIC14") (libsource (lib "AnalogIC") (part "LM339")))
    (comp (ref "U3")
      (value "OPA177GS,DNI")
      (footprint "SOIC8")
      (description "FET Operational Amplifier")
      (fields (field (name "PUBLISHER") "Altium Limited"))
      (libsource (lib "AnalogIC") (part "Op Amp_1ch"))
    )
    (comp (ref "U4")
      (value "STM32F103RBT6")
      (footprint "LQFP64")
      (description "STM32 ARM-based 32-bit MCU with 128 Kbytes Flash, 64-pin LQFP, Industrial Temperature")
      (fields (field (name "PUBLISHER") "*"))
      (libsource (lib "CPU") (part "STM32F103RBT6"))
    )
    (comp (ref "U6") (value "ISO1050") (footprint "SOP8-DUB") (libsource (lib "General") (part "ISO1050")))
    (comp (ref "U8")
      (value "ULN2803AFWG")
      (footprint "SOIC18-DW")
      (libsource (lib "AnalogIC") (part "ULN2803"))
    )
    (comp (ref "U9")
      (value "74HCT245")
      (footprint "GeneralPcblib V0.1:TSSOP20")
      (libsource (lib "DigtalIC") (part "74HC245"))
    )
    (comp (ref "U10")
      (value "ULN2803AFWG")
      (footprint "SOIC18-DW")
      (libsource (lib "AnalogIC") (part "ULN2803"))
    )
    (comp (ref "U11")
      (value "AD623ARZ,DNI")
      (footprint "SOIC8")
      (description "仪表放大器")
      (fields (field (name "PUBLISHER") "Altium Limited"))
      (libsource (lib "AnalogIC") (part "Op Amp_Instrumentation"))
    )
    (comp (ref "U12")
      (value "74HCT245")
      (footprint "GeneralPcblib V0.1:TSSOP20")
      (libsource (lib "DigtalIC") (part "74HC245"))
    )
    (comp (ref "U13")
      (value "74HCT245")
      (footprint "GeneralPcblib V0.1:TSSOP20")
      (libsource (lib "DigtalIC") (part "74HC245"))
    )
    (comp (ref "U16")
      (value "74HCT245")
      (footprint "GeneralPcblib V0.1:TSSOP20")
      (libsource (lib "DigtalIC") (part "74HC245"))
    )
    (comp (ref "U18")
      (value "REF3040")
      (footprint "SOT233")
      (description "电压参考")
      (libsource (lib "AnalogIC") (part "REF3040"))
    )
    (comp (ref "U19")
      (value "AD623ARZ")
      (footprint "SOIC8")
      (description "仪表放大器")
      (fields (field (name "PUBLISHER") "Altium Limited"))
      (libsource (lib "AnalogIC") (part "Op Amp_Instrumentation"))
    )
    (comp (ref "U21")
      (value "74HCT245")
      (footprint "GeneralPcblib V0.1:TSSOP20")
      (libsource (lib "DigtalIC") (part "74HC245"))
    )
    (comp (ref "VR3")
      (value "10K POT")
      (footprint "VR3296")
      (description "Potentiometer")
      (libsource (lib "DiscreteCom") (part "POT1B"))
    )
    (comp (ref "Y2")
      (value "8Mhz")
      (footprint "HC-49S")
      (description "Crystal")
      (libsource (lib "*") (part "CRYSTAL"))
    )
  )
  (nets
    (net (code "1") (name "/AC_CTR2") (class "Default")
      (node (ref "J6") (pin "1") (pinfunction "1_1") (pintype "passive"))
      (node (ref "RP2") (pin "4") (pinfunction "4_4") (pintype "passive"))
      (node (ref "U21") (pin "15") (pinfunction "B4_15") (pintype "passive"))
    )
    (net (code "2") (name "/AC_CTR19") (class "Default")
      (node (ref "RP2") (pin "6") (pinfunction "6_6") (pintype "passive"))
      (node (ref "U21") (pin "16") (pinfunction "B3_16") (pintype "passive"))
    )
    (net (code "3") (name "/AC_CTR20") (class "Default")
      (node (ref "RP1") (pin "4") (pinfunction "4_4") (pintype "passive"))
      (node (ref "U21") (pin "12") (pinfunction "B7_12") (pintype "passive"))
    )
    (net (code "4") (name "/AC_CTR31") (class "Default")
      (node (ref "J6") (pin "3") (pinfunction "3_3") (pintype "passive"))
      (node (ref "RP2") (pin "2") (pinfunction "2_2") (pintype "passive"))
      (node (ref "U21") (pin "14") (pinfunction "B5_14") (pintype "passive"))
    )
    (net (code "5") (name "/AC_CTR32") (class "Default")
      (node (ref "J6") (pin "5") (pinfunction "5_5") (pintype "passive"))
      (node (ref "RP1") (pin "6") (pinfunction "6_6") (pintype "passive"))
      (node (ref "U21") (pin "13") (pinfunction "B6_13") (pintype "passive"))
    )
    (net (code "6") (name "/AC_CTR33") (class "Default")
      (node (ref "J6") (pin "4") (pinfunction "4_4") (pintype "passive"))
      (node (ref "RP1") (pin "2") (pinfunction "2_2") (pintype "passive"))
      (node (ref "U21") (pin "11") (pinfunction "B8_11") (pintype "passive"))
    )
    (net (code "7") (name "/Bath_SIN+") (class "Default")
      (node (ref "P1") (pin "16") (pinfunction "16_16") (pintype "passive"))
      (node (ref "R42") (pin "2") (pinfunction "2_2") (pintype "passive"))
    )
    (net (code "8") (name "/Bath_SIN-") (class "Default")
      (node (ref "C20") (pin "1") (pinfunction "1_1") (pintype "passive"))
      (node (ref "P1") (pin "15") (pinfunction "15_15") (pintype "passive"))
      (node (ref "R47") (pin "1") (pinfunction "1_1") (pintype "passive"))
    )
    (net (code "9") (name "/CANH") (class "Default")
      (node (ref "CAN") (pin "3") (pintype "passive"))
      (node (ref "ESD1") (pin "2") (pinfunction "2_2") (pintype "passive"))
      (node (ref "U6") (pin "7") (pinfunction "CANH_7") (pintype "passive"))
    )
    (net (code "10") (name "/CANL") (class "Default")
      (node (ref "CAN") (pin "4") (pinfunction "4_4") (pintype "passive"))
      (node (ref "ESD1") (pin "1") (pinfunction "1_1") (pintype "passive"))
      (node (ref "U6") (pin "6") (pinfunction "CANL_6") (pintype "passive"))
    )
    (net (code "11") (name "/DCM_CTR1") (class "Default")
      (node (ref "Q3") (pin "4") (pinfunction "G_4") (pintype "passive"))
      (node (ref "U4") (pin "61") (pinfunction "PB8/TIM4_CH3/I2C1_SCL/CANRX_61") (pintype "bidirectional"))
    )
    (net (code "12") (name "/DCM_CTR2") (class "Default")
      (node (ref "Q3") (pin "2") (pinfunction "G_2") (pintype "passive"))
      (node (ref "U4") (pin "62") (pinfunction "PB9/TIM4_CH4/I2C1_SDA/CANTX_62") (pintype "bidirectional"))
    )
    (net (code "13") (name "/Heat_Pin") (class "Default")
      (node (ref "U21") (pin "2") (pinfunction "A1_2") (pintype "passive"))
      (node (ref "U21") (pin "3") (pinfunction "A2_3") (pintype "passive"))
      (node (ref "U4") (pin "42") (pinfunction "PA9/USART1_TX/TIM1_CH2_42") (pintype "bidirectional"))
    )
    (net (code "14") (name "/Heat_out") (class "Default")
      (node (ref "J6") (pin "7") (pinfunction "7_7") (pintype "passive"))
      (node (ref "U21") (pin "17") (pinfunction "B2_17") (pintype "passive"))
    )
    (net (code "15") (name "/IO1") (class "Default")
      (node (ref "CP2") (pin "2") (pinfunction "2_2") (pintype "passive"))
      (node (ref "D8") (pin "K") (pinfunction "K_K") (pintype "passive"))
      (node (ref "R28") (pin "1") (pinfunction "1_1") (pintype "passive"))
      (node (ref "R63") (pin "2") (pinfunction "2_2") (pintype "passive"))
      (node (ref "TP4") (pin "1") (pinfunction "1_1") (pintype "passive"))
      (node (ref "TVS2") (pin "2") (pinfunction "2_2") (pintype "passive"))
      (node (ref "U2") (pin "2") (pinfunction "out_2") (pintype "passive"))
    )
    (net (code "16") (name "/IO2") (class "Default")
      (node (ref "CP2") (pin "4") (pinfunction "4_4") (pintype "passive"))
      (node (ref "P1") (pin "14") (pinfunction "14_14") (pintype "passive"))
      (node (ref "R28") (pin "3") (pinfunction "3_3") (pintype "passive"))
      (node (ref "TVS2") (pin "1") (pinfunction "1_1") (pintype "passive"))
    )
    (net (code "17") (name "/IO3") (class "Default")
      (node (ref "CP2") (pin "6") (pinfunction "6_6") (pintype "passive"))
      (node (ref "P1") (pin "12") (pinfunction "12_12") (pintype "passive"))
      (node (ref "R28") (pin "5") (pinfunction "5_5") (pintype "passive"))
      (node (ref "TVS1") (pin "2") (pinfunction "2_2") (pintype "passive"))
    )
    (net (code "18") (name "/IO4") (class "Default")
      (node (ref "CP2") (pin "8") (pinfunction "8_8") (pintype "passive"))
      (node (ref "P1") (pin "10") (pinfunction "10_10") (pintype "passive"))
      (node (ref "R28") (pin "7") (pinfunction "7_7") (pintype "passive"))
      (node (ref "TVS1") (pin "1") (pinfunction "1_1") (pintype "passive"))
    )
    (net (code "19") (name "/IO5") (class "Default")
      (node (ref "CP1") (pin "2") (pinfunction "2_2") (pintype "passive"))
      (node (ref "P1") (pin "8") (pinfunction "8_8") (pintype "passive"))
      (node (ref "R29") (pin "1") (pinfunction "1_1") (pintype "passive"))
      (node (ref "TVS3") (pin "2") (pinfunction "2_2") (pintype "passive"))
    )
    (net (code "20") (name "/IO6") (class "Default")
      (node (ref "CP1") (pin "4") (pinfunction "4_4") (pintype "passive"))
      (node (ref "P1") (pin "6") (pinfunction "6_6") (pintype "passive"))
      (node (ref "R29") (pin "3") (pinfunction "3_3") (pintype "passive"))
      (node (ref "TVS3") (pin "1") (pinfunction "1_1") (pintype "passive"))
    )
    (net (code "21") (name "/IO7") (class "Default")
      (node (ref "CP1") (pin "6") (pinfunction "6_6") (pintype "passive"))
      (node (ref "P1") (pin "4") (pinfunction "4_4") (pintype "passive"))
      (node (ref "R29") (pin "5") (pinfunction "5_5") (pintype "passive"))
      (node (ref "TVS4") (pin "2") (pinfunction "2_2") (pintype "passive"))
    )
    (net (code "22") (name "/IO8") (class "Default")
      (node (ref "CP1") (pin "8") (pinfunction "8_8") (pintype "passive"))
      (node (ref "P1") (pin "2") (pinfunction "2_2") (pintype "passive"))
      (node (ref "R29") (pin "7") (pinfunction "7_7") (pintype "passive"))
      (node (ref "TVS4") (pin "1") (pinfunction "1_1") (pintype "passive"))
    )
    (net (code "23") (name "/PRESS_IN") (class "Default")
      (node (ref "C7") (pin "2") (pinfunction "2_2") (pintype "passive"))
      (node (ref "R4") (pin "1") (pinfunction "1_1") (pintype "passive"))
      (node (ref "U4") (pin "10") (pinfunction "PC2/ADC12_INI12_10") (pintype "bidirectional"))
    )
    (net (code "24") (name "/PRESS_SW1") (class "Default")
      (node (ref "J2") (pin "3") (pinfunction "3_3") (pintype "passive"))
      (node (ref "R12") (pin "1") (pinfunction "1_1") (pintype "passive"))
      (node (ref "R19") (pin "2") (pinfunction "2_2") (pintype "passive"))
    )
    (net (code "25") (name "/PRESS_SW2") (class "Default")
      (node (ref "J2") (pin "4") (pinfunction "4_4") (pintype "passive"))
    )
    (net (code "26") (name "/PT100_IN1") (class "Default")
      (node (ref "J9") (pin "1") (pinfunction "1_1") (pintype "passive"))
      (node (ref "J9") (pin "3") (pinfunction "3_3") (pintype "passive"))
      (node (ref "R44") (pin "2") (pinfunction "2_2") (pintype "passive"))
      (node (ref "U19") (pin "3") (pinfunction "IN+_3") (pintype "input"))
    )
    (net (code "27") (name "/PT100_IN2") (class "Default")
      (node (ref "J8,DNI") (pin "1") (pinfunction "1_1") (pintype "passive"))
      (node (ref "J8,DNI") (pin "3") (pinfunction "3_3") (pintype "passive"))
      (node (ref "R32") (pin "2") (pinfunction "2_2") (pintype "passive"))
      (node (ref "U11") (pin "3") (pinfunction "IN+_3") (pintype "input"))
    )
    (net (code "28") (name "/PV1") (class "Default")
      (node (ref "U12") (pin "7") (pinfunction "A6_7") (pintype "passive"))
      (node (ref "U4") (pin "35") (pinfunction "PB14/SPI2_MISO/TIM1_CH2N/USART3_RTS_35") (pintype "bidirectional"))
    )
    (net (code "29") (name "/PV1B") (class "Default")
      (node (ref "R13") (pin "2") (pinfunction "2_2") (pintype "passive"))
      (node (ref "U21") (pin "4") (pinfunction "A3_4") (pintype "passive"))
    )
    (net (code "30") (name "/PV2") (class "Default")
      (node (ref "U12") (pin "8") (pinfunction "A7_8") (pintype "passive"))
      (node (ref "U4") (pin "34") (pinfunction "PB13/SPI2_SCK/I2S2_CK/USART3_CTS/TIM1_CH1N_34") (pintype "bidirectional"))
    )
    (net (code "31") (name "/PV2B") (class "Default")
      (node (ref "R12") (pin "2") (pinfunction "2_2") (pintype "passive"))
      (node (ref "R3") (pin "2") (pinfunction "2_2") (pintype "passive"))
      (node (ref "U21") (pin "5") (pinfunction "A4_5") (pintype "passive"))
    )
    (net (code "32") (name "/PV2_AC") (class "Default")
      (node (ref "R3") (pin "1") (pinfunction "1_1") (pintype "passive"))
      (node (ref "U4") (pin "40") (pinfunction "PC9/TIM3_CH4_40") (pintype "bidirectional"))
    )
    (net (code "33") (name "/PV3") (class "Default")
      (node (ref "U12") (pin "9") (pinfunction "A8_9") (pintype "passive"))
      (node (ref "U4") (pin "33") (pinfunction "PB12/SPI2_NSS/I2C2_SMBA/USART3_CK/TIM1_BKIN_33") (pintype "bidirectional"))
    )
    (net (code "34") (name "/PV4") (class "Default")
      (node (ref "U4") (pin "30") (pinfunction "PB11/I2C2_SDA/USART3_RX/TIM2_CH4_30") (pintype "bidirectional"))
      (node (ref "U9") (pin "2") (pinfunction "A1_2") (pintype "passive"))
    )
    (net (code "35") (name "/PV5") (class "Default")
      (node (ref "U4") (pin "29") (pinfunction "PB10/I2C2_SCL/USART3_TX/TIM2_CH3_29") (pintype "bidirectional"))
      (node (ref "U9") (pin "3") (pinfunction "A2_3") (pintype "passive"))
    )
    (net (code "36") (name "/PV5B") (class "Default")
      (node (ref "R33") (pin "2") (pinfunction "2_2") (pintype "passive"))
      (node (ref "U21") (pin "8") (pinfunction "A7_8") (pintype "passive"))
    )
    (net (code "37") (name "/PV6") (class "Default")
      (node (ref "U4") (pin "27") (pinfunction "PB1/ADC12_IN9/TIM3_CH4/TIM1_CH3N_27") (pintype "bidirectional"))
      (node (ref "U9") (pin "4") (pinfunction "A3_4") (pintype "passive"))
    )
    (net (code "38") (name "/PV7") (class "Default")
      (node (ref "U4") (pin "26") (pinfunction "PB0/ADC12_IN8/TIM3_CH3/TIM1_CH2N_26") (pintype "bidirectional"))
      (node (ref "U9") (pin "5") (pinfunction "A4_5") (pintype "passive"))
    )
    (net (code "39") (name "/PV8") (class "Default")
      (node (ref "U4") (pin "25") (pinfunction "PC5/ADC12_INI15_25") (pintype "bidirectional"))
      (node (ref "U9") (pin "6") (pinfunction "A5_6") (pintype "passive"))
    )
    (net (code "40") (name "/PV9") (class "Default")
      (node (ref "U4") (pin "24") (pinfunction "PC4/ADC12_INI14_24") (pintype "bidirectional"))
      (node (ref "U9") (pin "7") (pinfunction "A6_7") (pintype "passive"))
    )
    (net (code "41") (name "/PV10") (class "Default")
      (node (ref "U4") (pin "23") (pinfunction "PA7/SPI1_MOSI/ADC12_IN7/TIM3_CH2/TIM1_CH1N_23") (pintype "bidirectional"))
      (node (ref "U9") (pin "8") (pinfunction "A7_8") (pintype "passive"))
    )
    (net (code "42") (name "/PV11") (class "Default")
      (node (ref "U4") (pin "22") (pinfunction "PA6/SPI1_MISO/ADC12_IN6/TIM3_CH1/TIM1_BKIN_22") (pintype "bidirectional"))
      (node (ref "U9") (pin "9") (pinfunction "A8_9") (pintype "passive"))
    )
    (net (code "43") (name "/PV12") (class "Default")
      (node (ref "U12") (pin "2") (pinfunction "A1_2") (pintype "passive"))
      (node (ref "U4") (pin "21") (pinfunction "PA5/SPI1_SCK/ADC12/IN5_21") (pintype "bidirectional"))
    )
    (net (code "44") (name "/PV13") (class "Default")
      (node (ref "U12") (pin "3") (pinfunction "A2_3") (pintype "passive"))
      (node (ref "U4") (pin "20") (pinfunction "PA4/SPI1_NSS/USART2_CK/ADC12_IN4_20") (pintype "bidirectional"))
    )
    (net (code "45") (name "/PV14") (class "Default")
      (node (ref "U12") (pin "4") (pinfunction "A3_4") (pintype "passive"))
      (node (ref "U4") (pin "17") (pinfunction "PA3/USATR2_RX/ADC12_IN3/TIM2_CH4_17") (pintype "bidirectional"))
    )
    (net (code "46") (name "/PV15") (class "Default")
      (node (ref "U13") (pin "3") (pinfunction "A2_3") (pintype "passive"))
      (node (ref "U4") (pin "16") (pinfunction "PA2/USATR2_TX/ADC12_IN2/TIM2_CH3_16") (pintype "bidirectional"))
    )
    (net (code "47") (name "/PV16") (class "Default")
      (node (ref "U13") (pin "4") (pinfunction "A3_4") (pintype "passive"))
      (node (ref "U4") (pin "15") (pinfunction "PA1/USART2_RTS/AD12_IN1/TIM2_CH2_15") (pintype "bidirectional"))
    )
    (net (code "48") (name "/PV17") (class "Default")
      (node (ref "U13") (pin "5") (pinfunction "A4_5") (pintype "passive"))
      (node (ref "U4") (pin "14") (pinfunction "PA0/WKUP/USART2_CTS/ADC12_IN0/TIM2_CH1_ETR_14") (pintype "bidirectional"))
    )
    (net (code "49") (name "/PV18") (class "Default")
      (node (ref "U13") (pin "2") (pinfunction "A1_2") (pintype "passive"))
      (node (ref "U4") (pin "59") (pinfunction "PB7/I2C1_SDA/TIM4_CH2/USART1_RX_59") (pintype "bidirectional"))
    )
    (net (code "50") (name "/PV19_AC") (class "Default")
      (node (ref "Q1") (pin "2") (pinfunction "G_2") (pintype "passive"))
      (node (ref "R13") (pin "1") (pinfunction "1_1") (pintype "passive"))
      (node (ref "U4") (pin "41") (pinfunction "PA8/USART1_CK/TIM1_CH1/MCO_41") (pintype "bidirectional"))
    )
    (net (code "51") (name "/PV20B") (class "Default")
      (node (ref "Q1") (pin "4") (pinfunction "G_4") (pintype "passive"))
      (node (ref "R36") (pin "2") (pinfunction "2_2") (pintype "passive"))
    )
    (net (code "52") (name "/PV20_AC") (class "Default")
      (node (ref "R33") (pin "1") (pinfunction "1_1") (pintype "passive"))
      (node (ref "R36") (pin "1") (pinfunction "1_1") (pintype "passive"))
      (node (ref "U4") (pin "37") (pinfunction "PC6/TIM3_CH1_37") (pintype "bidirectional"))
    )
    (net (code "53") (name "/PV31_AC") (class "Default")
      (node (ref "U21") (pin "6") (pinfunction "A5_6") (pintype "passive"))
      (node (ref "U4") (pin "39") (pinfunction "PC8/TIM3_CH3_39") (pintype "bidirectional"))
    )
    (net (code "54") (name "/PV32_AC") (class "Default")
      (node (ref "U21") (pin "7") (pinfunction "A6_7") (pintype "passive"))
      (node (ref "U4") (pin "38") (pinfunction "PC7/TIM3_CH2_38") (pintype "bidirectional"))
    )
    (net (code "55") (name "/PV33_AC") (class "Default")
      (node (ref "U21") (pin "9") (pinfunction "A8_9") (pintype "passive"))
      (node (ref "U4") (pin "36") (pinfunction "PB15/SPI2_MOSI/TIM1_CH3N_36") (pintype "bidirectional"))
    )
    (net (code "56") (name "/PVB1") (class "Default")
      (node (ref "U12") (pin "13") (pinfunction "B6_13") (pintype "passive"))
      (node (ref "U8") (pin "6") (pinfunction "IN6_6") (pintype "passive"))
    )
    (net (code "57") (name "/PVB2") (class "Default")
      (node (ref "U12") (pin "12") (pinfunction "B7_12") (pintype "passive"))
      (node (ref "U8") (pin "7") (pinfunction "IN7_7") (pintype "passive"))
    )
    (net (code "58") (name "/PVB3") (class "Default")
      (node (ref "U12") (pin "11") (pinfunction "B8_11") (pintype "passive"))
      (node (ref "U8") (pin "8") (pinfunction "IN8_8") (pintype "passive"))
    )
    (net (code "59") (name "/PVB4") (class "Default")
      (node (ref "U10") (pin "1") (pinfunction "IN1_1") (pintype "passive"))
      (node (ref "U9") (pin "18") (pinfunction "B1_18") (pintype "passive"))
    )
    (net (code "60") (name "/PVB5") (class "Default")
      (node (ref "U10") (pin "2") (pinfunction "IN2_2") (pintype "passive"))
      (node (ref "U9") (pin "17") (pinfunction "B2_17") (pintype "passive"))
    )
    (net (code "61") (name "/PVB6") (class "Default")
      (node (ref "U10") (pin "3") (pinfunction "IN3_3") (pintype "passive"))
      (node (ref "U9") (pin "16") (pinfunction "B3_16") (pintype "passive"))
    )
    (net (code "62") (name "/PVB7") (class "Default")
      (node (ref "U10") (pin "4") (pinfunction "IN4_4") (pintype "passive"))
      (node (ref "U9") (pin "15") (pinfunction "B4_15") (pintype "passive"))
    )
    (net (code "63") (name "/PVB8") (class "Default")
      (node (ref "U10") (pin "5") (pinfunction "IN5_5") (pintype "passive"))
      (node (ref "U9") (pin "14") (pinfunction "B5_14") (pintype "passive"))
    )
    (net (code "64") (name "/PVB9") (class "Default")
      (node (ref "U10") (pin "6") (pinfunction "IN6_6") (pintype "passive"))
      (node (ref "U9") (pin "13") (pinfunction "B6_13") (pintype "passive"))
    )
    (net (code "65") (name "/PVB10") (class "Default")
      (node (ref "U10") (pin "7") (pinfunction "IN7_7") (pintype "passive"))
      (node (ref "U9") (pin "12") (pinfunction "B7_12") (pintype "passive"))
    )
    (net (code "66") (name "/PVB11") (class "Default")
      (node (ref "U10") (pin "8") (pinfunction "IN8_8") (pintype "passive"))
      (node (ref "U9") (pin "11") (pinfunction "B8_11") (pintype "passive"))
    )
    (net (code "67") (name "/PVB12") (class "Default")
      (node (ref "U12") (pin "18") (pinfunction "B1_18") (pintype "passive"))
      (node (ref "U8") (pin "1") (pinfunction "IN1_1") (pintype "passive"))
    )
    (net (code "68") (name "/PVB13") (class "Default")
      (node (ref "U12") (pin "17") (pinfunction "B2_17") (pintype "passive"))
      (node (ref "U8") (pin "2") (pinfunction "IN2_2") (pintype "passive"))
    )
    (net (code "69") (name "/PVB14") (class "Default")
      (node (ref "U12") (pin "16") (pinfunction "B3_16") (pintype "passive"))
      (node (ref "U8") (pin "3") (pinfunction "IN3_3") (pintype "passive"))
    )
    (net (code "70") (name "/PVB15") (class "Default")
      (node (ref "Q4") (pin "4") (pinfunction "G_4") (pintype "passive"))
      (node (ref "U13") (pin "17") (pinfunction "B2_17") (pintype "passive"))
    )
    (net (code "71") (name "/PVB16") (class "Default")
      (node (ref "Q2") (pin "2") (pinfunction "G_2") (pintype "passive"))
      (node (ref "U13") (pin "16") (pinfunction "B3_16") (pintype "passive"))
    )
    (net (code "72") (name "/PVB17") (class "Default")
      (node (ref "Q2") (pin "4") (pinfunction "G_4") (pintype "passive"))
      (node (ref "U13") (pin "15") (pinfunction "B4_15") (pintype "passive"))
    )
    (net (code "73") (name "/PVB18") (class "Default")
      (node (ref "Q4") (pin "2") (pinfunction "G_2") (pintype "passive"))
      (node (ref "U13") (pin "18") (pinfunction "B1_18") (pintype "passive"))
    )
    (net (code "74") (name "/PVO1") (class "Default")
      (node (ref "HL1") (pin "K") (pinfunction "K_K") (pintype "passive"))
      (node (ref "J3") (pin "2") (pinfunction "2_2") (pintype "passive"))
      (node (ref "U8") (pin "13") (pinfunction "OUT6_13") (pintype "passive"))
    )
    (net (code "75") (name "/PVO2") (class "Default")
      (node (ref "HL2") (pin "K") (pinfunction "K_K") (pintype "passive"))
      (node (ref "J3") (pin "4") (pinfunction "4_4") (pintype "passive"))
      (node (ref "U8") (pin "12") (pinfunction "OUT7_12") (pintype "passive"))
    )
    (net (code "76") (name "/PVO3") (class "Default")
      (node (ref "HL3") (pin "K") (pinfunction "K_K") (pintype "passive"))
      (node (ref "J3") (pin "6") (pinfunction "6_6") (pintype "passive"))
      (node (ref "U8") (pin "11") (pinfunction "OUT8_11") (pintype "passive"))
    )
    (net (code "77") (name "/PVO4") (class "Default")
      (node (ref "HL4") (pin "K") (pinfunction "K_K") (pintype "passive"))
      (node (ref "P2") (pin "1") (pinfunction "1_1") (pintype "passive"))
      (node (ref "U10") (pin "18") (pinfunction "OUT1_18") (pintype "passive"))
    )
    (net (code "78") (name "/PVO5") (class "Default")
      (node (ref "HL5") (pin "K") (pinfunction "K_K") (pintype "passive"))
      (node (ref "P2") (pin "3") (pinfunction "3_3") (pintype "passive"))
      (node (ref "U10") (pin "17") (pinfunction "OUT2_17") (pintype "passive"))
    )
    (net (code "79") (name "/PVO6") (class "Default")
      (node (ref "HL6") (pin "K") (pinfunction "K_K") (pintype "passive"))
      (node (ref "P2") (pin "5") (pinfunction "5_5") (pintype "passive"))
      (node (ref "U10") (pin "16") (pinfunction "OUT3_16") (pintype "passive"))
    )
    (net (code "80") (name "/PVO7") (class "Default")
      (node (ref "HL7") (pin "K") (pinfunction "K_K") (pintype "passive"))
      (node (ref "P2") (pin "7") (pinfunction "7_7") (pintype "passive"))
      (node (ref "U10") (pin "15") (pinfunction "OUT4_15") (pintype "passive"))
    )
    (net (code "81") (name "/PVO8") (class "Default")
      (node (ref "HL8") (pin "K") (pinfunction "K_K") (pintype "passive"))
      (node (ref "P2") (pin "9") (pinfunction "9_9") (pintype "passive"))
      (node (ref "U10") (pin "14") (pinfunction "OUT5_14") (pintype "passive"))
    )
    (net (code "82") (name "/PVO9") (class "Default")
      (node (ref "HL9") (pin "K") (pinfunction "K_K") (pintype "passive"))
      (node (ref "P2") (pin "11") (pinfunction "11_11") (pintype "passive"))
      (node (ref "U10") (pin "13") (pinfunction "OUT6_13") (pintype "passive"))
    )
    (net (code "83") (name "/PVO10") (class "Default")
      (node (ref "HL10") (pin "K") (pinfunction "K_K") (pintype "passive"))
      (node (ref "P2") (pin "13") (pinfunction "13_13") (pintype "passive"))
      (node (ref "U10") (pin "12") (pinfunction "OUT7_12") (pintype "passive"))
    )
    (net (code "84") (name "/PVO11") (class "Default")
      (node (ref "HL11") (pin "K") (pinfunction "K_K") (pintype "passive"))
      (node (ref "P2") (pin "15") (pinfunction "15_15") (pintype "passive"))
      (node (ref "U10") (pin "11") (pinfunction "OUT8_11") (pintype "passive"))
    )
    (net (code "85") (name "/PVO12") (class "Default")
      (node (ref "HL12") (pin "K") (pinfunction "K_K") (pintype "passive"))
      (node (ref "P2") (pin "17") (pinfunction "17_17") (pintype "passive"))
      (node (ref "U8") (pin "18") (pinfunction "OUT1_18") (pintype "passive"))
    )
    (net (code "86") (name "/PVO13") (class "Default")
      (node (ref "HL13") (pin "K") (pinfunction "K_K") (pintype "passive"))
      (node (ref "P2") (pin "19") (pinfunction "19_19") (pintype "passive"))
      (node (ref "U8") (pin "17") (pinfunction "OUT2_17") (pintype "passive"))
    )
    (net (code "87") (name "/PVO14") (class "Default")
      (node (ref "HL14") (pin "K") (pinfunction "K_K") (pintype "passive"))
      (node (ref "P2") (pin "21") (pinfunction "21_21") (pintype "passive"))
      (node (ref "U8") (pin "16") (pinfunction "OUT3_16") (pintype "passive"))
    )
    (net (code "88") (name "/PVO15") (class "Default")
      (node (ref "D6") (pin "A") (pinfunction "A_A") (pintype "passive"))
      (node (ref "HL15") (pin "K") (pinfunction "K_K") (pintype "passive"))
      (node (ref "J3") (pin "8") (pinfunction "8_8") (pintype "passive"))
      (node (ref "Q4") (pin "5") (pinfunction "D_5") (pintype "passive"))
      (node (ref "Q4") (pin "6") (pinfunction "D_6") (pintype "passive"))
    )
    (net (code "89") (name "/PVO16") (class "Default")
      (node (ref "D5") (pin "A") (pinfunction "A_A") (pintype "passive"))
      (node (ref "HL16") (pin "K") (pinfunction "K_K") (pintype "passive"))
      (node (ref "J3") (pin "10") (pinfunction "10_10") (pintype "passive"))
      (node (ref "Q2") (pin "7") (pinfunction "D_7") (pintype "passive"))
      (node (ref "Q2") (pin "8") (pinfunction "D_8") (pintype "passive"))
    )
    (net (code "90") (name "/PVO17") (class "Default")
      (node (ref "D4") (pin "A") (pinfunction "A_A") (pintype "passive"))
      (node (ref "HL17") (pin "K") (pinfunction "K_K") (pintype "passive"))
      (node (ref "J3") (pin "12") (pinfunction "12_12") (pintype "passive"))
      (node (ref "Q2") (pin "5") (pinfunction "D_5") (pintype "passive"))
      (node (ref "Q2") (pin "6") (pinfunction "D_6") (pintype "passive"))
    )
    (net (code "91") (name "/PVO18") (class "Default")
      (node (ref "D7") (pin "A") (pinfunction "A_A") (pintype "passive"))
      (node (ref "HL18") (pin "K") (pinfunction "K_K") (pintype "passive"))
      (node (ref "P2") (pin "23") (pinfunction "23_23") (pintype "passive"))
      (node (ref "P2") (pin "25") (pinfunction "25_25") (pintype "passive"))
      (node (ref "Q4") (pin "7") (pinfunction "D_7") (pintype "passive"))
      (node (ref "Q4") (pin "8") (pinfunction "D_8") (pintype "passive"))
    )
    (net (code "93") (name "/PVO19_AC") (class "Default")
      (node (ref "D3") (pin "A") (pinfunction "A_A") (pintype "passive"))
      (node (ref "HL19") (pin "K") (pinfunction "K_K") (pintype "passive"))
      (node (ref "J3") (pin "14") (pinfunction "14_14") (pintype "passive"))
      (node (ref "Q1") (pin "7") (pinfunction "D_7") (pintype "passive"))
      (node (ref "Q1") (pin "8") (pinfunction "D_8") (pintype "passive"))
    )
    (net (code "95") (name "/PVO20_AC") (class "Default")
      (node (ref "D1") (pin "A") (pinfunction "A_A") (pintype "passive"))
      (node (ref "HL20") (pin "K") (pinfunction "K_K") (pintype "passive"))
      (node (ref "J3") (pin "16") (pinfunction "16_16") (pintype "passive"))
      (node (ref "Q1") (pin "5") (pinfunction "D_5") (pintype "passive"))
      (node (ref "Q1") (pin "6") (pinfunction "D_6") (pintype "passive"))
    )
    (net (code "96") (name "/PVO21") (class "Default")
      (node (ref "D10") (pin "A") (pinfunction "A_A") (pintype "passive"))
      (node (ref "J3") (pin "18") (pinfunction "18_18") (pintype "passive"))
      (node (ref "Q5") (pin "5") (pinfunction "D_5") (pintype "passive"))
      (node (ref "Q5") (pin "6") (pinfunction "D_6") (pintype "passive"))
    )
    (net (code "97") (name "/PVO22") (class "Default")
      (node (ref "D11") (pin "A") (pinfunction "A_A") (pintype "passive"))
      (node (ref "J3") (pin "20") (pinfunction "20_20") (pintype "passive"))
      (node (ref "Q5") (pin "7") (pinfunction "D_7") (pintype "passive"))
      (node (ref "Q5") (pin "8") (pinfunction "D_8") (pintype "passive"))
    )
    (net (code "99") (name "/PV_21") (class "Default")
      (node (ref "Q5") (pin "2") (pinfunction "G_2") (pintype "passive"))
      (node (ref "Q5") (pin "4") (pinfunction "G_4") (pintype "passive"))
      (node (ref "U4") (pin "4") (pinfunction "PC15-OSC32_OUT_4") (pintype "bidirectional"))
    )
    (net (code "100") (name "/SIO_IN1") (class "Default")
      (node (ref "U16") (pin "18") (pinfunction "B1_18") (pintype "passive"))
      (node (ref "U4") (pin "51") (pinfunction "PC10/USART3_TX_51") (pintype "bidirectional"))
    )
    (net (code "101") (name "/SIO_IN2") (class "Default")
      (node (ref "U16") (pin "17") (pinfunction "B2_17") (pintype "passive"))
      (node (ref "U4") (pin "52") (pinfunction "PC11/USART3_RX_52") (pintype "bidirectional"))
    )
    (net (code "102") (name "/SIO_IN3") (class "Default")
      (node (ref "U16") (pin "16") (pinfunction "B3_16") (pintype "passive"))
      (node (ref "U4") (pin "53") (pinfunction "PC12/USART3_CK_53") (pintype "bidirectional"))
    )
    (net (code "103") (name "/SIO_IN4") (class "Default")
      (node (ref "U16") (pin "15") (pinfunction "B4_15") (pintype "passive"))
      (node (ref "U4") (pin "54") (pinfunction "PD2_54") (pintype "bidirectional"))
    )
    (net (code "104") (name "/SIO_IN5") (class "Default")
      (node (ref "U16") (pin "14") (pinfunction "B5_14") (pintype "passive"))
      (node (ref "U4") (pin "57") (pinfunction "PB5/I2C1_SMBA/TIM3_CH2/SPI1_MOSI_57") (pintype "bidirectional"))
    )
    (net (code "105") (name "/SIO_IN6") (class "Default")
      (node (ref "U16") (pin "13") (pinfunction "B6_13") (pintype "passive"))
      (node (ref "U4") (pin "58") (pinfunction "PB6/I2C1_SCL/TIM4_CH1/USART1_TX_58") (pintype "bidirectional"))
    )
    (net (code "106") (name "/SIO_IN7") (class "Default")
      (node (ref "U16") (pin "12") (pinfunction "B7_12") (pintype "passive"))
      (node (ref "U4") (pin "2") (pinfunction "PC13-TAMPER-RTC_2") (pintype "bidirectional"))
    )
    (net (code "107") (name "/SIO_IN8") (class "Default")
      (node (ref "U16") (pin "11") (pinfunction "B8_11") (pintype "passive"))
      (node (ref "U4") (pin "3") (pinfunction "PC14-OSC32_IN_3") (pintype "bidirectional"))
    )
    (net (code "108") (name "/S_IN1") (class "Default")
      (node (ref "R11") (pin "1") (pinfunction "1_1") (pintype "passive"))
      (node (ref "R28") (pin "2") (pinfunction "2_2") (pintype "passive"))
      (node (ref "U16") (pin "2") (pinfunction "A1_2") (pintype "passive"))
    )
    (net (code "109") (name "/S_IN2") (class "Default")
      (node (ref "R20") (pin "1") (pinfunction "1_1") (pintype "passive"))
      (node (ref "R28") (pin "4") (pinfunction "4_4") (pintype "passive"))
      (node (ref "U16") (pin "3") (pinfunction "A2_3") (pintype "passive"))
    )
    (net (code "110") (name "/S_IN3") (class "Default")
      (node (ref "R27") (pin "1") (pinfunction "1_1") (pintype "passive"))
      (node (ref "R28") (pin "6") (pinfunction "6_6") (pintype "passive"))
      (node (ref "U16") (pin "4") (pinfunction "A3_4") (pintype "passive"))
    )
    (net (code "111") (name "/S_IN4") (class "Default")
      (node (ref "R28") (pin "8") (pinfunction "8_8") (pintype "passive"))
      (node (ref "R35") (pin "1") (pinfunction "1_1") (pintype "passive"))
      (node (ref "U16") (pin "5") (pinfunction "A4_5") (pintype "passive"))
    )
    (net (code "112") (name "/S_IN5") (class "Default")
      (node (ref "R26") (pin "1") (pinfunction "1_1") (pintype "passive"))
      (node (ref "R29") (pin "2") (pinfunction "2_2") (pintype "passive"))
      (node (ref "U16") (pin "6") (pinfunction "A5_6") (pintype "passive"))
    )
    (net (code "113") (name "/S_IN6") (class "Default")
      (node (ref "R26") (pin "3") (pinfunction "3_3") (pintype "passive"))
      (node (ref "R29") (pin "4") (pinfunction "4_4") (pintype "passive"))
      (node (ref "U16") (pin "7") (pinfunction "A6_7") (pintype "passive"))
    )
    (net (code "114") (name "/S_IN7") (class "Default")
      (node (ref "R26") (pin "5") (pinfunction "5_5") (pintype "passive"))
      (node (ref "R29") (pin "6") (pinfunction "6_6") (pintype "passive"))
      (node (ref "U16") (pin "8") (pinfunction "A7_8") (pintype "passive"))
    )
    (net (code "115") (name "/S_IN8") (class "Default")
      (node (ref "R26") (pin "7") (pinfunction "7_7") (pintype "passive"))
      (node (ref "R29") (pin "8") (pinfunction "8_8") (pintype "passive"))
      (node (ref "U16") (pin "9") (pinfunction "A8_9") (pintype "passive"))
    )
    (net (code "116") (name "/T_BOOT0") (class "Default")
      (node (ref "R50") (pin "1") (pinfunction "1_1") (pintype "passive"))
      (node (ref "U4") (pin "60") (pinfunction "BOOT0_60") (pintype "input"))
    )
    (net (code "117") (name "/T_BOOT1") (class "Default")
      (node (ref "R51") (pin "1") (pinfunction "1_1") (pintype "passive"))
      (node (ref "U4") (pin "28") (pinfunction "PB2/BOOT1_28") (pintype "bidirectional"))
    )
    (net (code "118") (name "/T_CAN_RX") (class "Default")
      (node (ref "R7") (pin "1") (pinfunction "1_1") (pintype "passive"))
      (node (ref "U4") (pin "44") (pinfunction "PA11/USART1_CTS/CAN_RX/TIM1_CH4/USBDM_44") (pintype "bidirectional"))
      (node (ref "U6") (pin "2") (pinfunction "RXD_2") (pintype "passive"))
    )
    (net (code "119") (name "/T_CAN_TX") (class "Default")
      (node (ref "R8") (pin "1") (pinfunction "1_1") (pintype "passive"))
      (node (ref "U4") (pin "45") (pinfunction "PA12/USART2/RTS/CAN_TX/TIM1_ETR/USBDP_45") (pintype "bidirectional"))
      (node (ref "U6") (pin "3") (pinfunction "TXD_3") (pintype "passive"))
    )
    (net (code "120") (name "/T_NRST") (class "Default")
      (node (ref "C42") (pin "1") (pinfunction "1_1") (pintype "passive"))
      (node (ref "R16") (pin "1") (pinfunction "1_1") (pintype "passive"))
      (node (ref "U4") (pin "7") (pinfunction "NRST_7") (pintype "bidirectional"))
    )
    (net (code "121") (name "/T_NTRST") (class "Default")
      (node (ref "U4") (pin "56") (pinfunction "PB4/JNTRST_56") (pintype "bidirectional"))
    )
    (net (code "122") (name "/T_TCK{slash}SWCLK") (class "Default")
      (node (ref "CON2") (pin "4") (pinfunction "4_4") (pintype "passive"))
      (node (ref "R10") (pin "1") (pinfunction "1_1") (pintype "passive"))
      (node (ref "U4") (pin "49") (pinfunction "PA14/JTCK/SWCLK_49") (pintype "bidirectional"))
    )
    (net (code "123") (name "/T_TDI") (class "Default")
      (node (ref "U4") (pin "50") (pinfunction "PA15/JTDI_50") (pintype "bidirectional"))
    )
    (net (code "124") (name "/T_TDO") (class "Default")
      (node (ref "U4") (pin "55") (pinfunction "PB3/JTDO_55") (pintype "bidirectional"))
    )
    (net (code "125") (name "/T_TMS{slash}SWDIO") (class "Default")
      (node (ref "CON2") (pin "3") (pinfunction "3_3") (pintype "passive"))
      (node (ref "U4") (pin "46") (pinfunction "PA13/JTMS/SWDIO_46") (pintype "bidirectional"))
    )
    (net (code "126") (name "/Temp_IN1") (class "Default")
      (node (ref "C82") (pin "2") (pinfunction "2_2") (pintype "passive"))
      (node (ref "R53") (pin "1") (pinfunction "1_1") (pintype "passive"))
      (node (ref "U4") (pin "8") (pinfunction "PC0/ADC12_INI10_8") (pintype "bidirectional"))
    )
    (net (code "127") (name "/Temp_IN2") (class "Default")
      (node (ref "C74") (pin "2") (pinfunction "2_2") (pintype "passive"))
      (node (ref "R90") (pin "1") (pinfunction "1_1") (pintype "passive"))
      (node (ref "U4") (pin "9") (pinfunction "PC1/ADC12_INI11_9") (pintype "bidirectional"))
    )
    (net (code "128") (name "/Temp_offset") (class "Default")
      (node (ref "C115") (pin "1") (pinfunction "1_1") (pintype "passive"))
      (node (ref "U4") (pin "11") (pinfunction "PC3/ADC12_INI13_11") (pintype "bidirectional"))
      (node (ref "VR3") (pin "3") (pinfunction "W_3") (pintype "passive"))
    )
    (net (code "129") (name "/VS-") (class "Default")
      (node (ref "R1") (pin "2") (pinfunction "2_2") (pintype "passive"))
      (node (ref "R24") (pin "2") (pinfunction "2_2") (pintype "passive"))
      (node (ref "R9") (pin "2") (pinfunction "2_2") (pintype "passive"))
      (node (ref "U11") (pin "4") (pinfunction "V-_4") (pintype "power_in"))
      (node (ref "U19") (pin "4") (pinfunction "V-_4") (pintype "power_in"))
    )
    (net (code "130") (name "/WLED") (class "Default")
      (node (ref "R49") (pin "2") (pinfunction "2_2") (pintype "passive"))
      (node (ref "U4") (pin "43") (pinfunction "PA10/USART1_RX/TIM1_CH3_43") (pintype "bidirectional"))
    )
    (net (code "131") (name "A+5V") (class "Default")
      (node (ref "C100") (pin "1") (pinfunction "1_1") (pintype "passive"))
      (node (ref "C18") (pin "1") (pinfunction "1_1") (pintype "passive"))
      (node (ref "C34") (pin "2") (pinfunction "2_2") (pintype "passive"))
      (node (ref "C73") (pin "1") (pinfunction "1_1") (pintype "passive"))
      (node (ref "C8") (pin "1") (pinfunction "1_1") (pintype "passive"))
      (node (ref "P1") (pin "18") (pinfunction "18_18") (pintype "passive"))
      (node (ref "P1") (pin "20") (pinfunction "20_20") (pintype "passive"))
      (node (ref "R11") (pin "2") (pinfunction "2_2") (pintype "passive"))
      (node (ref "R19") (pin "1") (pinfunction "1_1") (pintype "passive"))
      (node (ref "R20") (pin "2") (pinfunction "2_2") (pintype "passive"))
      (node (ref "R27") (pin "2") (pinfunction "2_2") (pintype "passive"))
      (node (ref "R35") (pin "2") (pinfunction "2_2") (pintype "passive"))
      (node (ref "R37") (pin "2") (pinfunction "2_2") (pintype "passive"))
      (node (ref "R39") (pin "1") (pinfunction "1_1") (pintype "passive"))
      (node (ref "R40") (pin "2") (pinfunction "2_2") (pintype "passive"))
      (node (ref "R45") (pin "2") (pinfunction "2_2") (pintype "passive"))
      (node (ref "R48") (pin "1") (pinfunction "1_1") (pintype "passive"))
      (node (ref "R61") (pin "1") (pinfunction "1_1") (pintype "passive"))
      (node (ref "R65") (pin "2") (pinfunction "2_2") (pintype "passive"))
      (node (ref "R66") (pin "2") (pinfunction "2_2") (pintype "passive"))
      (node (ref "U11") (pin "7") (pinfunction "V+_7") (pintype "power_in"))
      (node (ref "U18") (pin "1") (pinfunction "IN_1") (pintype "passive"))
      (node (ref "U19") (pin "7") (pinfunction "V+_7") (pintype "power_in"))
      (node (ref "U2") (pin "3") (pinfunction "VCC_3") (pintype "passive"))
      (node (ref "U3") (pin "7") (pinfunction "V+_7") (pintype "power_in"))
    )
    (net (code "132") (name "A-5V") (class "Default")
      (node (ref "C14") (pin "1") (pinfunction "1_1") (pintype "passive"))
      (node (ref "R24") (pin "1") (pinfunction "1_1") (pintype "passive"))
      (node (ref "U3") (pin "4") (pinfunction "V-_4") (pintype "power_in"))
    )
    (net (code "133") (name "CANG") (class "Default")
      (node (ref "C36") (pin "1") (pinfunction "1_1") (pintype "passive"))
      (node (ref "CAN") (pin "2") (pintype "passive"))
      (node (ref "ESD1") (pin "3") (pinfunction "3_3") (pintype "passive"))
      (node (ref "U6") (pin "5") (pinfunction "GND2_5") (pintype "passive"))
    )
    (net (code "134") (name "CAN_5V") (class "Default")
      (node (ref "C36") (pin "2") (pinfunction "2_2") (pintype "passive"))
      (node (ref "CAN") (pin "1") (pintype "passive"))
      (node (ref "U6") (pin "8") (pinfunction "VCC2_8") (pintype "passive"))
    )
    (net (code "135") (name "Net-(AC1-PadA)") (class "Default")
      (node (ref "AC1") (pin "A") (pinfunction "A_A") (pintype "passive"))
      (node (ref "RP2") (pin "3") (pinfunction "3_3") (pintype "passive"))
    )
    (net (code "136") (name "Net-(AC2-PadA)") (class "Default")
      (node (ref "AC2") (pin "A") (pinfunction "A_A") (pintype "passive"))
      (node (ref "RP2") (pin "5") (pinfunction "5_5") (pintype "passive"))
    )
    (net (code "137") (name "Net-(AC3-PadA)") (class "Default")
      (node (ref "AC3") (pin "A") (pinfunction "A_A") (pintype "passive"))
      (node (ref "RP2") (pin "7") (pinfunction "7_7") (pintype "passive"))
    )
    (net (code "138") (name "Net-(AC4-PadA)") (class "Default")
      (node (ref "AC4") (pin "A") (pinfunction "A_A") (pintype "passive"))
      (node (ref "RP1") (pin "1") (pinfunction "1_1") (pintype "passive"))
    )
    (net (code "139") (name "Net-(AC5-PadA)") (class "Default")
      (node (ref "AC5") (pin "A") (pinfunction "A_A") (pintype "passive"))
      (node (ref "RP1") (pin "3") (pinfunction "3_3") (pintype "passive"))
    )
    (net (code "140") (name "Net-(AC6-PadA)") (class "Default")
      (node (ref "AC6") (pin "A") (pinfunction "A_A") (pintype "passive"))
      (node (ref "RP1") (pin "5") (pinfunction "5_5") (pintype "passive"))
    )
    (net (code "141") (name "Net-(C21-Pad1)") (class "Default")
      (node (ref "C21") (pin "1") (pinfunction "1_1") (pintype "passive"))
      (node (ref "R48") (pin "2") (pinfunction "2_2") (pintype "passive"))
      (node (ref "R55") (pin "1") (pinfunction "1_1") (pintype "passive"))
      (node (ref "R60") (pin "1") (pinfunction "1_1") (pintype "passive"))
    )
    (net (code "142") (name "Net-(D8-PadA)") (class "Default")
      (node (ref "D8") (pin "A") (pinfunction "A_A") (pintype "passive"))
      (node (ref "R40") (pin "1") (pinfunction "1_1") (pintype "passive"))
    )
    (net (code "143") (name "Net-(D16-PadA)") (class "Default")
      (node (ref "D16") (pin "A") (pinfunction "A_A") (pintype "passive"))
      (node (ref "J1") (pin "2") (pinfunction "2_2") (pintype "passive"))
      (node (ref "Q3") (pin "5") (pinfunction "D_5") (pintype "passive"))
      (node (ref "Q3") (pin "6") (pinfunction "D_6") (pintype "passive"))
    )
    (net (code "144") (name "Net-(D17-PadA)") (class "Default")
      (node (ref "D17") (pin "A") (pinfunction "A_A") (pintype "passive"))
      (node (ref "J4") (pin "2") (pinfunction "2_2") (pintype "passive"))
      (node (ref "Q3") (pin "7") (pinfunction "D_7") (pintype "passive"))
      (node (ref "Q3") (pin "8") (pinfunction "D_8") (pintype "passive"))
    )
    (net (code "145") (name "Net-(HL1-PadA)") (class "Default")
      (node (ref "HL1") (pin "A") (pinfunction "A_A") (pintype "passive"))
      (node (ref "R23") (pin "8") (pinfunction "8_8") (pintype "passive"))
    )
    (net (code "146") (name "Net-(HL2-PadA)") (class "Default")
      (node (ref "HL2") (pin "A") (pinfunction "A_A") (pintype "passive"))
      (node (ref "R25") (pin "2") (pinfunction "2_2") (pintype "passive"))
    )
    (net (code "147") (name "Net-(HL3-PadA)") (class "Default")
      (node (ref "HL3") (pin "A") (pinfunction "A_A") (pintype "passive"))
      (node (ref "R25") (pin "4") (pinfunction "4_4") (pintype "passive"))
    )
    (net (code "148") (name "Net-(HL4-PadA)") (class "Default")
      (node (ref "HL4") (pin "A") (pinfunction "A_A") (pintype "passive"))
      (node (ref "R14") (pin "2") (pinfunction "2_2") (pintype "passive"))
    )
    (net (code "149") (name "Net-(HL5-PadA)") (class "Default")
      (node (ref "HL5") (pin "A") (pinfunction "A_A") (pintype "passive"))
      (node (ref "R14") (pin "4") (pinfunction "4_4") (pintype "passive"))
    )
    (net (code "150") (name "Net-(HL6-PadA)") (class "Default")
      (node (ref "HL6") (pin "A") (pinfunction "A_A") (pintype "passive"))
      (node (ref "R14") (pin "6") (pinfunction "6_6") (pintype "passive"))
    )
    (net (code "151") (name "Net-(HL7-PadA)") (class "Default")
      (node (ref "HL7") (pin "A") (pinfunction "A_A") (pintype "passive"))
      (node (ref "R14") (pin "8") (pinfunction "8_8") (pintype "passive"))
    )
    (net (code "152") (name "Net-(HL8-PadA)") (class "Default")
      (node (ref "HL8") (pin "A") (pinfunction "A_A") (pintype "passive"))
      (node (ref "R21") (pin "2") (pinfunction "2_2") (pintype "passive"))
    )
    (net (code "153") (name "Net-(HL9-PadA)") (class "Default")
      (node (ref "HL9") (pin "A") (pinfunction "A_A") (pintype "passive"))
      (node (ref "R21") (pin "4") (pinfunction "4_4") (pintype "passive"))
    )
    (net (code "154") (name "Net-(HL10-PadA)") (class "Default")
      (node (ref "HL10") (pin "A") (pinfunction "A_A") (pintype "passive"))
      (node (ref "R21") (pin "6") (pinfunction "6_6") (pintype "passive"))
    )
    (net (code "155") (name "Net-(HL11-PadA)") (class "Default")
      (node (ref "HL11") (pin "A") (pinfunction "A_A") (pintype "passive"))
      (node (ref "R21") (pin "8") (pinfunction "8_8") (pintype "passive"))
    )
    (net (code "156") (name "Net-(HL12-PadA)") (class "Default")
      (node (ref "HL12") (pin "A") (pinfunction "A_A") (pintype "passive"))
      (node (ref "R22") (pin "2") (pinfunction "2_2") (pintype "passive"))
    )
    (net (code "157") (name "Net-(HL13-PadA)") (class "Default")
      (node (ref "HL13") (pin "A") (pinfunction "A_A") (pintype "passive"))
      (node (ref "R22") (pin "4") (pinfunction "4_4") (pintype "passive"))
    )
    (net (code "158") (name "Net-(HL14-PadA)") (class "Default")
      (node (ref "HL14") (pin "A") (pinfunction "A_A") (pintype "passive"))
      (node (ref "R22") (pin "6") (pinfunction "6_6") (pintype "passive"))
    )
    (net (code "159") (name "Net-(HL15-PadA)") (class "Default")
      (node (ref "HL15") (pin "A") (pinfunction "A_A") (pintype "passive"))
      (node (ref "R22") (pin "8") (pinfunction "8_8") (pintype "passive"))
    )
    (net (code "160") (name "Net-(HL16-PadA)") (class "Default")
      (node (ref "HL16") (pin "A") (pinfunction "A_A") (pintype "passive"))
      (node (ref "R23") (pin "2") (pinfunction "2_2") (pintype "passive"))
    )
    (net (code "161") (name "Net-(HL17-PadA)") (class "Default")
      (node (ref "HL17") (pin "A") (pinfunction "A_A") (pintype "passive"))
      (node (ref "R23") (pin "4") (pinfunction "4_4") (pintype "passive"))
    )
    (net (code "162") (name "Net-(HL18-PadA)") (class "Default")
      (node (ref "HL18") (pin "A") (pinfunction "A_A") (pintype "passive"))
      (node (ref "R23") (pin "6") (pinfunction "6_6") (pintype "passive"))
    )
    (net (code "163") (name "Net-(HL19-PadA)") (class "Default")
      (node (ref "HL19") (pin "A") (pinfunction "A_A") (pintype "passive"))
      (node (ref "R25") (pin "6") (pinfunction "6_6") (pintype "passive"))
    )
    (net (code "164") (name "Net-(HL20-PadA)") (class "Default")
      (node (ref "HL20") (pin "A") (pinfunction "A_A") (pintype "passive"))
      (node (ref "R25") (pin "8") (pinfunction "8_8") (pintype "passive"))
    )
    (net (code "165") (name "Net-(HL25-PadA)") (class "Default")
      (node (ref "HL25") (pin "A") (pinfunction "A_A") (pintype "passive"))
      (node (ref "R49") (pin "1") (pinfunction "1_1") (pintype "passive"))
    )
    (net (code "166") (name "Net-(HT-PadA)") (class "Default")
      (node (ref "HT") (pin "A") (pinfunction "A_A") (pintype "passive"))
      (node (ref "RP2") (pin "1") (pinfunction "1_1") (pintype "passive"))
    )
    (net (code "167") (name "Net-(J2-Pad5)") (class "Default")
      (node (ref "J2") (pin "5") (pinfunction "5_5") (pintype "passive"))
      (node (ref "R5") (pin "1") (pinfunction "1_1") (pintype "passive"))
    )
    (net (code "168") (name "Net-(P1-Pad19)") (class "Default")
      (node (ref "P1") (pin "19") (pinfunction "19_19") (pintype "passive"))
      (node (ref "R37") (pin "1") (pinfunction "1_1") (pintype "passive"))
    )
    (net (code "169") (name "Net-(R39-Pad2)") (class "Default")
      (node (ref "R39") (pin "2") (pinfunction "2_2") (pintype "passive"))
      (node (ref "R41") (pin "1") (pinfunction "1_1") (pintype "passive"))
    )
    (net (code "170") (name "Net-(R61-Pad2)") (class "Default")
      (node (ref "R61") (pin "2") (pinfunction "2_2") (pintype "passive"))
      (node (ref "R62") (pin "1") (pinfunction "1_1") (pintype "passive"))
      (node (ref "R64") (pin "1") (pinfunction "1_1") (pintype "passive"))
    )
    (net (code "171") (name "Net-(U2A-+)") (class "Default")
      (node (ref "R55") (pin "2") (pinfunction "2_2") (pintype "passive"))
      (node (ref "R56") (pin "1") (pinfunction "1_1") (pintype "passive"))
      (node (ref "U2") (pin "7") (pinfunction "+_7") (pintype "passive"))
    )
    (net (code "172") (name "Net-(U2A--)") (class "Default")
      (node (ref "C19") (pin "1") (pinfunction "1_1") (pintype "passive"))
      (node (ref "R41") (pin "2") (pinfunction "2_2") (pintype "passive"))
      (node (ref "R42") (pin "1") (pinfunction "1_1") (pintype "passive"))
      (node (ref "TP3") (pin "1") (pinfunction "1_1") (pintype "passive"))
      (node (ref "U2") (pin "6") (pinfunction "-_6") (pintype "passive"))
    )
    (net (code "173") (name "Net-(U2A-out)") (class "Default")
      (node (ref "R45") (pin "1") (pinfunction "1_1") (pintype "passive"))
      (node (ref "R46") (pin "1") (pinfunction "1_1") (pintype "passive"))
      (node (ref "R56") (pin "2") (pinfunction "2_2") (pintype "passive"))
      (node (ref "U2") (pin "1") (pinfunction "out_1") (pintype "passive"))
    )
    (net (code "174") (name "Net-(U2B-+)") (class "Default")
      (node (ref "R62") (pin "2") (pinfunction "2_2") (pintype "passive"))
      (node (ref "R63") (pin "1") (pinfunction "1_1") (pintype "passive"))
      (node (ref "U2") (pin "5") (pinfunction "+_5") (pintype "passive"))
    )
    (net (code "175") (name "Net-(U2B--)") (class "Default")
      (node (ref "R46") (pin "2") (pinfunction "2_2") (pintype "passive"))
      (node (ref "U2") (pin "4") (pinfunction "-_4") (pintype "passive"))
    )
    (net (code "176") (name "Net-(U2C--)") (class "Default")
      (node (ref "R67") (pin "1") (pinfunction "1_1") (pintype "passive"))
      (node (ref "U2") (pin "8") (pinfunction "-_8") (pintype "passive"))
    )
    (net (code "177") (name "Net-(U2C-out)") (class "Default")
      (node (ref "R65") (pin "1") (pinfunction "1_1") (pintype "passive"))
      (node (ref "U2") (pin "14") (pinfunction "out_14") (pintype "passive"))
    )
    (net (code "178") (name "Net-(U2D--)") (class "Default")
      (node (ref "R68") (pin "1") (pinfunction "1_1") (pintype "passive"))
      (node (ref "U2") (pin "10") (pinfunction "-_10") (pintype "passive"))
    )
    (net (code "179") (name "Net-(U2D-out)") (class "Default")
      (node (ref "R66") (pin "1") (pinfunction "1_1") (pintype "passive"))
      (node (ref "U2") (pin "13") (pinfunction "out_13") (pintype "passive"))
    )
    (net (code "180") (name "Net-(U3-IN+)") (class "Default")
      (node (ref "R5") (pin "2") (pinfunction "2_2") (pintype "passive"))
      (node (ref "R6") (pin "1") (pinfunction "1_1") (pintype "passive"))
      (node (ref "U3") (pin "3") (pinfunction "IN+_3") (pintype "input"))
    )
    (net (code "181") (name "Net-(U3-IN-)") (class "Default")
      (node (ref "R4") (pin "2") (pinfunction "2_2") (pintype "passive"))
      (node (ref "U3") (pin "2") (pinfunction "IN-_2") (pintype "input"))
      (node (ref "U3") (pin "6") (pinfunction "OUT_6") (pintype "output"))
    )
    (net (code "182") (name "Net-(U4-OSC_IN{slash}PD0)") (class "Default")
      (node (ref "C39") (pin "2") (pinfunction "2_2") (pintype "passive"))
      (node (ref "U4") (pin "5") (pinfunction "OSC_IN/PD0_5") (pintype "input"))
      (node (ref "Y2") (pin "2") (pinfunction "2_2") (pintype "passive"))
    )
    (net (code "183") (name "Net-(U4-OSC_OUT{slash}PD1)") (class "Default")
      (node (ref "C40") (pin "2") (pinfunction "2_2") (pintype "passive"))
      (node (ref "U4") (pin "6") (pinfunction "OSC_OUT/PD1_6") (pintype "output"))
      (node (ref "Y2") (pin "1") (pinfunction "1_1") (pintype "passive"))
    )
    (net (code "184") (name "Net-(U11-IN-)") (class "Default")
      (node (ref "R30") (pin "2") (pinfunction "2_2") (pintype "passive"))
      (node (ref "R34") (pin "2") (pinfunction "2_2") (pintype "passive"))
      (node (ref "R38") (pin "1") (pinfunction "1_1") (pintype "passive"))
      (node (ref "U11") (pin "2") (pinfunction "IN-_2") (pintype "input"))
    )
    (net (code "185") (name "Net-(U11-OS_NUL)") (class "Default")
      (node (ref "R2") (pin "2") (pinfunction "2_2") (pintype "passive"))
      (node (ref "U11") (pin "1") (pinfunction "OS_NUL_1") (pintype "passive"))
    )
    (net (code "186") (name "Net-(U11-OUT)") (class "Default")
      (node (ref "R90") (pin "2") (pinfunction "2_2") (pintype "passive"))
      (node (ref "U11") (pin "6") (pinfunction "OUT_6") (pintype "output"))
    )
    (net (code "187") (name "Net-(U11-TAB)") (class "Default")
      (node (ref "R2") (pin "1") (pinfunction "1_1") (pintype "passive"))
      (node (ref "U11") (pin "8") (pinfunction "TAB_8") (pintype "passive"))
    )
    (net (code "188") (name "Net-(U12-B4)") (class "Default")
      (node (ref "U12") (pin "15") (pinfunction "B4_15") (pintype "passive"))
      (node (ref "U8") (pin "4") (pinfunction "IN4_4") (pintype "passive"))
    )
    (net (code "189") (name "Net-(U12-B5)") (class "Default")
      (node (ref "U12") (pin "14") (pinfunction "B5_14") (pintype "passive"))
      (node (ref "U8") (pin "5") (pinfunction "IN5_5") (pintype "passive"))
    )
    (net (code "190") (name "Net-(U19-IN-)") (class "Default")
      (node (ref "R31") (pin "2") (pinfunction "2_2") (pintype "passive"))
      (node (ref "R52") (pin "2") (pinfunction "2_2") (pintype "passive"))
      (node (ref "R54") (pin "1") (pinfunction "1_1") (pintype "passive"))
      (node (ref "U19") (pin "2") (pinfunction "IN-_2") (pintype "input"))
    )
    (net (code "191") (name "Net-(U19-OS_NUL)") (class "Default")
      (node (ref "R43") (pin "2") (pinfunction "2_2") (pintype "passive"))
      (node (ref "U19") (pin "1") (pinfunction "OS_NUL_1") (pintype "passive"))
    )
    (net (code "192") (name "Net-(U19-OUT)") (class "Default")
      (node (ref "R53") (pin "2") (pinfunction "2_2") (pintype "passive"))
      (node (ref "U19") (pin "6") (pinfunction "OUT_6") (pintype "output"))
    )
    (net (code "193") (name "Net-(U19-TAB)") (class "Default")
      (node (ref "R43") (pin "1") (pinfunction "1_1") (pintype "passive"))
      (node (ref "U19") (pin "8") (pinfunction "TAB_8") (pintype "passive"))
    )
    (net (code "194") (name "Net-(U21-B1)") (class "Default")
      (node (ref "RP2") (pin "8") (pinfunction "8_8") (pintype "passive"))
      (node (ref "U21") (pin "18") (pinfunction "B1_18") (pintype "passive"))
    )
    (net (code "195") (name "PGND") (class "Default")
      (node (ref "AC1") (pin "K") (pinfunction "K_K") (pintype "passive"))
      (node (ref "AC2") (pin "K") (pinfunction "K_K") (pintype "passive"))
      (node (ref "AC3") (pin "K") (pinfunction "K_K") (pintype "passive"))
      (node (ref "AC4") (pin "K") (pinfunction "K_K") (pintype "passive"))
      (node (ref "AC5") (pin "K") (pinfunction "K_K") (pintype "passive"))
      (node (ref "AC6") (pin "K") (pinfunction "K_K") (pintype "passive"))
      (node (ref "C100") (pin "2") (pinfunction "2_2") (pintype "passive"))
      (node (ref "C105") (pin "1") (pinfunction "1_1") (pintype "passive"))
      (node (ref "C115") (pin "2") (pinfunction "2_2") (pintype "passive"))
      (node (ref "C14") (pin "2") (pinfunction "2_2") (pintype "passive"))
      (node (ref "C15") (pin "1") (pinfunction "1_1") (pintype "passive"))
      (node (ref "C16") (pin "1") (pinfunction "1_1") (pintype "passive"))
      (node (ref "C17") (pin "1") (pinfunction "1_1") (pintype "passive"))
      (node (ref "C18") (pin "2") (pinfunction "2_2") (pintype "passive"))
      (node (ref "C19") (pin "2") (pinfunction "2_2") (pintype "passive"))
      (node (ref "C20") (pin "2") (pinfunction "2_2") (pintype "passive"))
      (node (ref "C21") (pin "2") (pinfunction "2_2") (pintype "passive"))
      (node (ref "C34") (pin "1") (pinfunction "1_1") (pintype "passive"))
      (node (ref "C37") (pin "1") (pinfunction "1_1") (pintype "passive"))
      (node (ref "C39") (pin "1") (pinfunction "1_1") (pintype "passive"))
      (node (ref "C40") (pin "1") (pinfunction "1_1") (pintype "passive"))
      (node (ref "C42") (pin "2") (pinfunction "2_2") (pintype "passive"))
      (node (ref "C43") (pin "2") (pinfunction "2_2") (pintype "passive"))
      (node (ref "C46") (pin "2") (pinfunction "2_2") (pintype "passive"))
      (node (ref "C47") (pin "2") (pinfunction "2_2") (pintype "passive"))
      (node (ref "C50") (pin "2") (pinfunction "2_2") (pintype "passive"))
      (node (ref "C51") (pin "2") (pinfunction "2_2") (pintype "passive"))
      (node (ref "C52") (pin "2") (pinfunction "2_2") (pintype "passive"))
      (node (ref "C68") (pin "1") (pinfunction "1_1") (pintype "passive"))
      (node (ref "C69") (pin "2") (pinfunction "2_2") (pintype "passive"))
      (node (ref "C7") (pin "1") (pinfunction "1_1") (pintype "passive"))
      (node (ref "C73") (pin "2") (pinfunction "2_2") (pintype "passive"))
      (node (ref "C74") (pin "1") (pinfunction "1_1") (pintype "passive"))
      (node (ref "C78") (pin "1") (pinfunction "1_1") (pintype "passive"))
      (node (ref "C79") (pin "1") (pinfunction "1_1") (pintype "passive"))
      (node (ref "C8") (pin "2") (pinfunction "2_2") (pintype "passive"))
      (node (ref "C82") (pin "1") (pinfunction "1_1") (pintype "passive"))
      (node (ref "C9") (pin "1") (pinfunction "1_1") (pintype "passive"))
      (node (ref "CD1") (pin "2") (pinfunction "2_2") (pintype "passive"))
      (node (ref "CD2") (pin "2") (pinfunction "2_2") (pintype "passive"))
      (node (ref "CD3") (pin "2") (pinfunction "2_2") (pintype "passive"))
      (node (ref "CD4") (pin "2") (pinfunction "2_2") (pintype "passive"))
      (node (ref "CD9") (pin "2") (pinfunction "2_2") (pintype "passive"))
      (node (ref "CON2") (pin "2") (pinfunction "2_2") (pintype "passive"))
      (node (ref "CP1") (pin "1") (pinfunction "1_1") (pintype "passive"))
      (node (ref "CP1") (pin "3") (pinfunction "3_3") (pintype "passive"))
      (node (ref "CP1") (pin "5") (pinfunction "5_5") (pintype "passive"))
      (node (ref "CP1") (pin "7") (pinfunction "7_7") (pintype "passive"))
      (node (ref "CP2") (pin "1") (pinfunction "1_1") (pintype "passive"))
      (node (ref "CP2") (pin "3") (pinfunction "3_3") (pintype "passive"))
      (node (ref "CP2") (pin "5") (pinfunction "5_5") (pintype "passive"))
      (node (ref "CP2") (pin "7") (pinfunction "7_7") (pintype "passive"))
      (node (ref "HL25") (pin "K") (pinfunction "K_K") (pintype "passive"))
      (node (ref "HT") (pin "K") (pinfunction "K_K") (pintype "passive"))
      (node (ref "J2") (pin "2") (pinfunction "2_2") (pintype "passive"))
      (node (ref "J6") (pin "9") (pinfunction "9_9") (pintype "passive"))
      (node (ref "J8,DNI") (pin "2") (pinfunction "2_2") (pintype "passive"))
      (node (ref "J9") (pin "2") (pinfunction "2_2") (pintype "passive"))
      (node (ref "P1") (pin "1") (pinfunction "1_1") (pintype "passive"))
      (node (ref "P1") (pin "11") (pinfunction "11_11") (pintype "passive"))
      (node (ref "P1") (pin "13") (pinfunction "13_13") (pintype "passive"))
      (node (ref "P1") (pin "17") (pinfunction "17_17") (pintype "passive"))
      (node (ref "P1") (pin "3") (pinfunction "3_3") (pintype "passive"))
      (node (ref "P1") (pin "5") (pinfunction "5_5") (pintype "passive"))
      (node (ref "P1") (pin "7") (pinfunction "7_7") (pintype "passive"))
      (node (ref "P1") (pin "9") (pinfunction "9_9") (pintype "passive"))
      (node (ref "Q1") (pin "1") (pinfunction "S_1") (pintype "passive"))
      (node (ref "Q1") (pin "3") (pinfunction "S_3") (pintype "passive"))
      (node (ref "Q2") (pin "1") (pinfunction "S_1") (pintype "passive"))
      (node (ref "Q2") (pin "3") (pinfunction "S_3") (pintype "passive"))
      (node (ref "Q3") (pin "1") (pinfunction "S_1") (pintype "passive"))
      (node (ref "Q3") (pin "3") (pinfunction "S_3") (pintype "passive"))
      (node (ref "Q4") (pin "1") (pinfunction "S_1") (pintype "passive"))
      (node (ref "Q4") (pin "3") (pinfunction "S_3") (pintype "passive"))
      (node (ref "Q5") (pin "1") (pinfunction "S_1") (pintype "passive"))
      (node (ref "Q5") (pin "3") (pinfunction "S_3") (pintype "passive"))
      (node (ref "R1") (pin "1") (pinfunction "1_1") (pintype "passive"))
      (node (ref "R10") (pin "2") (pinfunction "2_2") (pintype "passive"))
      (node (ref "R30") (pin "1") (pinfunction "1_1") (pintype "passive"))
      (node (ref "R31") (pin "1") (pinfunction "1_1") (pintype "passive"))
      (node (ref "R38") (pin "2") (pinfunction "2_2") (pintype "passive"))
      (node (ref "R47") (pin "2") (pinfunction "2_2") (pintype "passive"))
      (node (ref "R50") (pin "2") (pinfunction "2_2") (pintype "passive"))
      (node (ref "R51") (pin "2") (pinfunction "2_2") (pintype "passive"))
      (node (ref "R54") (pin "2") (pinfunction "2_2") (pintype "passive"))
      (node (ref "R6") (pin "2") (pinfunction "2_2") (pintype "passive"))
      (node (ref "R60") (pin "2") (pinfunction "2_2") (pintype "passive"))
      (node (ref "R64") (pin "2") (pinfunction "2_2") (pintype "passive"))
      (node (ref "R67") (pin "2") (pinfunction "2_2") (pintype "passive"))
      (node (ref "R68") (pin "2") (pinfunction "2_2") (pintype "passive"))
      (node (ref "R9") (pin "1") (pinfunction "1_1") (pintype "passive"))
      (node (ref "TVS1") (pin "3") (pinfunction "3_3") (pintype "passive"))
      (node (ref "TVS2") (pin "3") (pinfunction "3_3") (pintype "passive"))
      (node (ref "TVS3") (pin "3") (pinfunction "3_3") (pintype "passive"))
      (node (ref "TVS4") (pin "3") (pinfunction "3_3") (pintype "passive"))
      (node (ref "U10") (pin "9") (pinfunction "GND_9") (pintype "passive"))
      (node (ref "U11") (pin "5") (pinfunction "REF_5") (pintype "passive"))
      (node (ref "U12") (pin "10") (pinfunction "GND_10") (pintype "passive"))
      (node (ref "U12") (pin "19") (pinfunction "~{OE}_19") (pintype "passive"))
      (node (ref "U13") (pin "10") (pinfunction "GND_10") (pintype "passive"))
      (node (ref "U13") (pin "19") (pinfunction "~{OE}_19") (pintype "passive"))
      (node (ref "U16") (pin "10") (pinfunction "GND_10") (pintype "passive"))
      (node (ref "U16") (pin "19") (pinfunction "~{OE}_19") (pintype "passive"))
      (node (ref "U18") (pin "3") (pinfunction "G_3") (pintype "passive"))
      (node (ref "U19") (pin "5") (pinfunction "REF_5") (pintype "passive"))
      (node (ref "U2") (pin "11") (pinfunction "+_11") (pintype "passive"))
      (node (ref "U2") (pin "12") (pinfunction "G_12") (pintype "passive"))
      (node (ref "U2") (pin "9") (pinfunction "+_9") (pintype "passive"))
      (node (ref "U21") (pin "10") (pinfunction "GND_10") (pintype "passive"))
      (node (ref "U21") (pin "19") (pinfunction "~{OE}_19") (pintype "passive"))
      (node (ref "U4") (pin "12") (pinfunction "VSSA_12") (pintype "power_in"))
      (node (ref "U4") (pin "18") (pinfunction "VSS_4_18") (pintype "power_in"))
      (node (ref "U4") (pin "31") (pinfunction "VSS_1_31") (pintype "power_in"))
      (node (ref "U4") (pin "47") (pinfunction "VSS_2_47") (pintype "power_in"))
      (node (ref "U4") (pin "63") (pinfunction "VSS_3_63") (pintype "power_in"))
      (node (ref "U6") (pin "4") (pinfunction "GND1_4") (pintype "passive"))
      (node (ref "U8") (pin "9") (pinfunction "GND_9") (pintype "passive"))
      (node (ref "U9") (pin "10") (pinfunction "GND_10") (pintype "passive"))
      (node (ref "U9") (pin "19") (pinfunction "~{OE}_19") (pintype "passive"))
      (node (ref "VR3") (pin "1") (pinfunction "1_1") (pintype "passive"))
    )
    (net (code "196") (name "VA_REF") (class "Default")
      (node (ref "C15") (pin "2") (pinfunction "2_2") (pintype "passive"))
      (node (ref "C79") (pin "2") (pinfunction "2_2") (pintype "passive"))
      (node (ref "R32") (pin "1") (pinfunction "1_1") (pintype "passive"))
      (node (ref "R34") (pin "1") (pinfunction "1_1") (pintype "passive"))
      (node (ref "R44") (pin "1") (pinfunction "1_1") (pintype "passive"))
      (node (ref "R52") (pin "1") (pinfunction "1_1") (pintype "passive"))
      (node (ref "U18") (pin "2") (pinfunction "OUT_2") (pintype "passive"))
    )
    (net (code "197") (name "VDD3.3B") (class "Default")
      (node (ref "C37") (pin "2") (pinfunction "2_2") (pintype "passive"))
      (node (ref "C46") (pin "1") (pinfunction "1_1") (pintype "passive"))
      (node (ref "C47") (pin "1") (pinfunction "1_1") (pintype "passive"))
      (node (ref "C50") (pin "1") (pinfunction "1_1") (pintype "passive"))
      (node (ref "C51") (pin "1") (pinfunction "1_1") (pintype "passive"))
      (node (ref "C69") (pin "1") (pinfunction "1_1") (pintype "passive"))
      (node (ref "C78") (pin "2") (pinfunction "2_2") (pintype "passive"))
      (node (ref "CON2") (pin "1") (pinfunction "1_1") (pintype "passive"))
      (node (ref "FB1") (pin "1") (pinfunction "1_1") (pintype "passive"))
      (node (ref "R16") (pin "2") (pinfunction "2_2") (pintype "passive"))
      (node (ref "R26") (pin "2") (pinfunction "2_2") (pintype "passive"))
      (node (ref "R26") (pin "4") (pinfunction "4_4") (pintype "passive"))
      (node (ref "R26") (pin "6") (pinfunction "6_6") (pintype "passive"))
      (node (ref "R26") (pin "8") (pinfunction "8_8") (pintype "passive"))
      (node (ref "R7") (pin "2") (pinfunction "2_2") (pintype "passive"))
      (node (ref "R8") (pin "2") (pinfunction "2_2") (pintype "passive"))
      (node (ref "U16") (pin "1") (pinfunction "DIR_1") (pintype "passive"))
      (node (ref "U16") (pin "20") (pinfunction "VCC_20") (pintype "passive"))
      (node (ref "U4") (pin "1") (pinfunction "VBAT_1") (pintype "power_in"))
      (node (ref "U4") (pin "19") (pinfunction "VDD_4_19") (pintype "power_in"))
      (node (ref "U4") (pin "32") (pinfunction "VDD_1_32") (pintype "power_in"))
      (node (ref "U4") (pin "48") (pinfunction "VDD_2_48") (pintype "power_in"))
      (node (ref "U4") (pin "64") (pinfunction "VDD_3_64") (pintype "power_in"))
      (node (ref "U6") (pin "1") (pinfunction "VCC1_1") (pintype "passive"))
      (node (ref "VR3") (pin "2") (pinfunction "2_2") (pintype "passive"))
    )
    (net (code "198") (name "VDD5V") (class "Default")
      (node (ref "C105") (pin "2") (pinfunction "2_2") (pintype "passive"))
      (node (ref "C16") (pin "2") (pinfunction "2_2") (pintype "passive"))
      (node (ref "C17") (pin "2") (pinfunction "2_2") (pintype "passive"))
      (node (ref "C9") (pin "2") (pinfunction "2_2") (pintype "passive"))
      (node (ref "J6") (pin "10") (pinfunction "10_10") (pintype "passive"))
      (node (ref "U12") (pin "1") (pinfunction "DIR_1") (pintype "passive"))
      (node (ref "U12") (pin "20") (pinfunction "VCC_20") (pintype "passive"))
      (node (ref "U13") (pin "1") (pinfunction "DIR_1") (pintype "passive"))
      (node (ref "U13") (pin "20") (pinfunction "VCC_20") (pintype "passive"))
      (node (ref "U21") (pin "1") (pinfunction "DIR_1") (pintype "passive"))
      (node (ref "U21") (pin "20") (pinfunction "VCC_20") (pintype "passive"))
      (node (ref "U9") (pin "1") (pinfunction "DIR_1") (pintype "passive"))
      (node (ref "U9") (pin "20") (pinfunction "VCC_20") (pintype "passive"))
    )
    (net (code "199") (name "VDD12") (class "Default")
      (node (ref "D16") (pin "K") (pinfunction "K_K") (pintype "passive"))
      (node (ref "D17") (pin "K") (pinfunction "K_K") (pintype "passive"))
      (node (ref "J1") (pin "1") (pinfunction "1_1") (pintype "passive"))
      (node (ref "J2") (pin "1") (pinfunction "1_1") (pintype "passive"))
      (node (ref "J4") (pin "1") (pinfunction "1_1") (pintype "passive"))
    )
    (net (code "200") (name "VDDA") (class "Default")
      (node (ref "C43") (pin "1") (pinfunction "1_1") (pintype "passive"))
      (node (ref "C68") (pin "2") (pinfunction "2_2") (pintype "passive"))
      (node (ref "FB1") (pin "2") (pinfunction "2_2") (pintype "passive"))
      (node (ref "U4") (pin "13") (pinfunction "VDDA_13") (pintype "power_in"))
    )
    (net (code "201") (name "VM") (class "Default")
      (node (ref "C52") (pin "1") (pinfunction "1_1") (pintype "passive"))
      (node (ref "CD1") (pin "1") (pinfunction "1_1") (pintype "passive"))
      (node (ref "CD2") (pin "1") (pinfunction "1_1") (pintype "passive"))
      (node (ref "CD3") (pin "1") (pinfunction "1_1") (pintype "passive"))
      (node (ref "CD4") (pin "1") (pinfunction "1_1") (pintype "passive"))
      (node (ref "CD9") (pin "1") (pinfunction "1_1") (pintype "passive"))
      (node (ref "D1") (pin "K") (pinfunction "K_K") (pintype "passive"))
      (node (ref "D10") (pin "K") (pinfunction "K_K") (pintype "passive"))
      (node (ref "D11") (pin "K") (pinfunction "K_K") (pintype "passive"))
      (node (ref "D3") (pin "K") (pinfunction "K_K") (pintype "passive"))
      (node (ref "D4") (pin "K") (pinfunction "K_K") (pintype "passive"))
      (node (ref "D5") (pin "K") (pinfunction "K_K") (pintype "passive"))
      (node (ref "D6") (pin "K") (pinfunction "K_K") (pintype "passive"))
      (node (ref "D7") (pin "K") (pinfunction "K_K") (pintype "passive"))
      (node (ref "J3") (pin "1") (pinfunction "1_1") (pintype "passive"))
      (node (ref "J3") (pin "11") (pinfunction "11_11") (pintype "passive"))
      (node (ref "J3") (pin "13") (pinfunction "13_13") (pintype "passive"))
      (node (ref "J3") (pin "15") (pinfunction "15_15") (pintype "passive"))
      (node (ref "J3") (pin "17") (pinfunction "17_17") (pintype "passive"))
      (node (ref "J3") (pin "19") (pinfunction "19_19") (pintype "passive"))
      (node (ref "J3") (pin "3") (pinfunction "3_3") (pintype "passive"))
      (node (ref "J3") (pin "5") (pinfunction "5_5") (pintype "passive"))
      (node (ref "J3") (pin "7") (pinfunction "7_7") (pintype "passive"))
      (node (ref "J3") (pin "9") (pinfunction "9_9") (pintype "passive"))
      (node (ref "P2") (pin "10") (pinfunction "10_10") (pintype "passive"))
      (node (ref "P2") (pin "12") (pinfunction "12_12") (pintype "passive"))
      (node (ref "P2") (pin "14") (pinfunction "14_14") (pintype "passive"))
      (node (ref "P2") (pin "16") (pinfunction "16_16") (pintype "passive"))
      (node (ref "P2") (pin "18") (pinfunction "18_18") (pintype "passive"))
      (node (ref "P2") (pin "2") (pinfunction "2_2") (pintype "passive"))
      (node (ref "P2") (pin "20") (pinfunction "20_20") (pintype "passive"))
      (node (ref "P2") (pin "22") (pinfunction "22_22") (pintype "passive"))
      (node (ref "P2") (pin "24") (pinfunction "24_24") (pintype "passive"))
      (node (ref "P2") (pin "26") (pinfunction "26_26") (pintype "passive"))
      (node (ref "P2") (pin "4") (pinfunction "4_4") (pintype "passive"))
      (node (ref "P2") (pin "6") (pinfunction "6_6") (pintype "passive"))
      (node (ref "P2") (pin "8") (pinfunction "8_8") (pintype "passive"))
      (node (ref "R14") (pin "1") (pinfunction "1_1") (pintype "passive"))
      (node (ref "R14") (pin "3") (pinfunction "3_3") (pintype "passive"))
      (node (ref "R14") (pin "5") (pinfunction "5_5") (pintype "passive"))
      (node (ref "R14") (pin "7") (pinfunction "7_7") (pintype "passive"))
      (node (ref "R21") (pin "1") (pinfunction "1_1") (pintype "passive"))
      (node (ref "R21") (pin "3") (pinfunction "3_3") (pintype "passive"))
      (node (ref "R21") (pin "5") (pinfunction "5_5") (pintype "passive"))
      (node (ref "R21") (pin "7") (pinfunction "7_7") (pintype "passive"))
      (node (ref "R22") (pin "1") (pinfunction "1_1") (pintype "passive"))
      (node (ref "R22") (pin "3") (pinfunction "3_3") (pintype "passive"))
      (node (ref "R22") (pin "5") (pinfunction "5_5") (pintype "passive"))
      (node (ref "R22") (pin "7") (pinfunction "7_7") (pintype "passive"))
      (node (ref "R23") (pin "1") (pinfunction "1_1") (pintype "passive"))
      (node (ref "R23") (pin "3") (pinfunction "3_3") (pintype "passive"))
      (node (ref "R23") (pin "5") (pinfunction "5_5") (pintype "passive"))
      (node (ref "R23") (pin "7") (pinfunction "7_7") (pintype "passive"))
      (node (ref "R25") (pin "1") (pinfunction "1_1") (pintype "passive"))
      (node (ref "R25") (pin "3") (pinfunction "3_3") (pintype "passive"))
      (node (ref "R25") (pin "5") (pinfunction "5_5") (pintype "passive"))
      (node (ref "R25") (pin "7") (pinfunction "7_7") (pintype "passive"))
      (node (ref "U10") (pin "10") (pinfunction "COM_10") (pintype "passive"))
      (node (ref "U8") (pin "10") (pinfunction "COM_10") (pintype "passive"))
    )
    (net (code "202") (name "unconnected-(J6-Pad2)") (class "Default")
      (node (ref "J6") (pin "2") (pinfunction "2_2") (pintype "passive"))
    )
    (net (code "203") (name "unconnected-(J6-Pad6)") (class "Default")
      (node (ref "J6") (pin "6") (pinfunction "6_6") (pintype "passive"))
    )
    (net (code "204") (name "unconnected-(J6-Pad8)") (class "Default")
      (node (ref "J6") (pin "8") (pinfunction "8_8") (pintype "passive"))
    )
    (net (code "205") (name "unconnected-(RP1-Pad7)") (class "Default")
      (node (ref "RP1") (pin "7") (pinfunction "7_7") (pintype "passive"))
    )
    (net (code "206") (name "unconnected-(RP1-Pad8)") (class "Default")
      (node (ref "RP1") (pin "8") (pinfunction "8_8") (pintype "passive"))
    )
    (net (code "207") (name "unconnected-(U3-OS_NUL-Pad1)") (class "Default")
      (node (ref "U3") (pin "1") (pinfunction "OS_NUL_1") (pintype "passive"))
    )
    (net (code "208") (name "unconnected-(U3-OS_NUL-Pad8)") (class "Default")
      (node (ref "U3") (pin "8") (pinfunction "OS_NUL_8") (pintype "passive"))
    )
    (net (code "209") (name "unconnected-(U3-TAB-Pad5)") (class "Default")
      (node (ref "U3") (pin "5") (pinfunction "TAB_5") (pintype "passive"))
    )
    (net (code "210") (name "unconnected-(U8-OUT4-Pad15)") (class "Default")
      (node (ref "U8") (pin "15") (pinfunction "OUT4_15") (pintype "passive"))
    )
    (net (code "211") (name "unconnected-(U8-OUT5-Pad14)") (class "Default")
      (node (ref "U8") (pin "14") (pinfunction "OUT5_14") (pintype "passive"))
    )
    (net (code "212") (name "unconnected-(U12-A4-Pad5)") (class "Default")
      (node (ref "U12") (pin "5") (pinfunction "A4_5") (pintype "passive"))
    )
    (net (code "213") (name "unconnected-(U12-A5-Pad6)") (class "Default")
      (node (ref "U12") (pin "6") (pinfunction "A5_6") (pintype "passive"))
    )
    (net (code "214") (name "unconnected-(U13-A5-Pad6)") (class "Default")
      (node (ref "U13") (pin "6") (pinfunction "A5_6") (pintype "passive"))
    )
    (net (code "215") (name "unconnected-(U13-A6-Pad7)") (class "Default")
      (node (ref "U13") (pin "7") (pinfunction "A6_7") (pintype "passive"))
    )
    (net (code "216") (name "unconnected-(U13-A7-Pad8)") (class "Default")
      (node (ref "U13") (pin "8") (pinfunction "A7_8") (pintype "passive"))
    )
    (net (code "217") (name "unconnected-(U13-A8-Pad9)") (class "Default")
      (node (ref "U13") (pin "9") (pinfunction "A8_9") (pintype "passive"))
    )
    (net (code "218") (name "unconnected-(U13-B5-Pad14)") (class "Default")
      (node (ref "U13") (pin "14") (pinfunction "B5_14") (pintype "passive"))
    )
    (net (code "219") (name "unconnected-(U13-B6-Pad13)") (class "Default")
      (node (ref "U13") (pin "13") (pinfunction "B6_13") (pintype "passive"))
    )
    (net (code "220") (name "unconnected-(U13-B7-Pad12)") (class "Default")
      (node (ref "U13") (pin "12") (pinfunction "B7_12") (pintype "passive"))
    )
    (net (code "221") (name "unconnected-(U13-B8-Pad11)") (class "Default")
      (node (ref "U13") (pin "11") (pinfunction "B8_11") (pintype "passive"))
    )
  )
)
